# offical_board.net
KiCad netlist of a schematic drawn in EAGLE
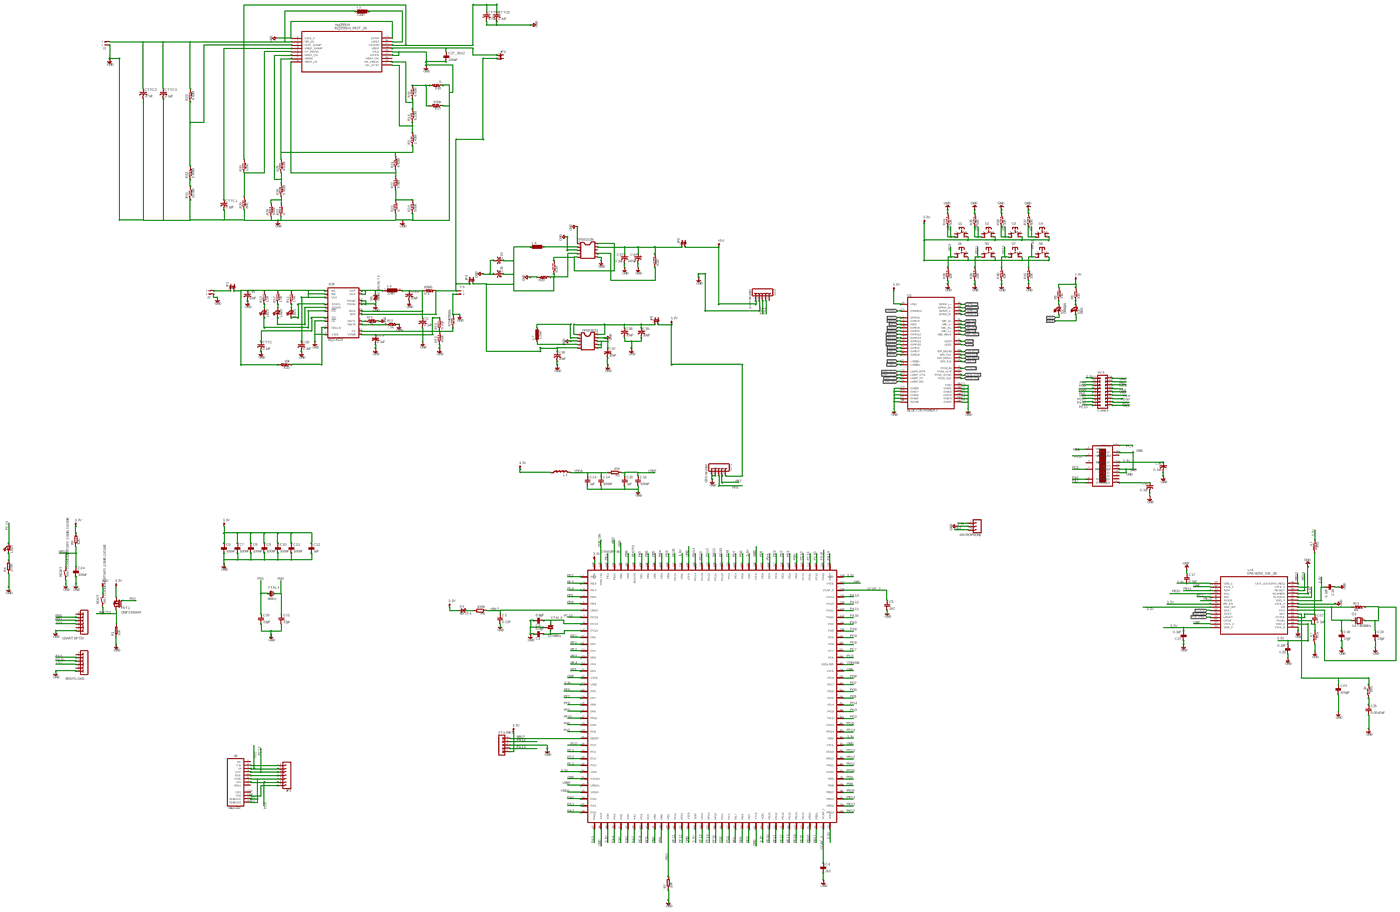
[diagram p0: schematic, sheet 1, overview]
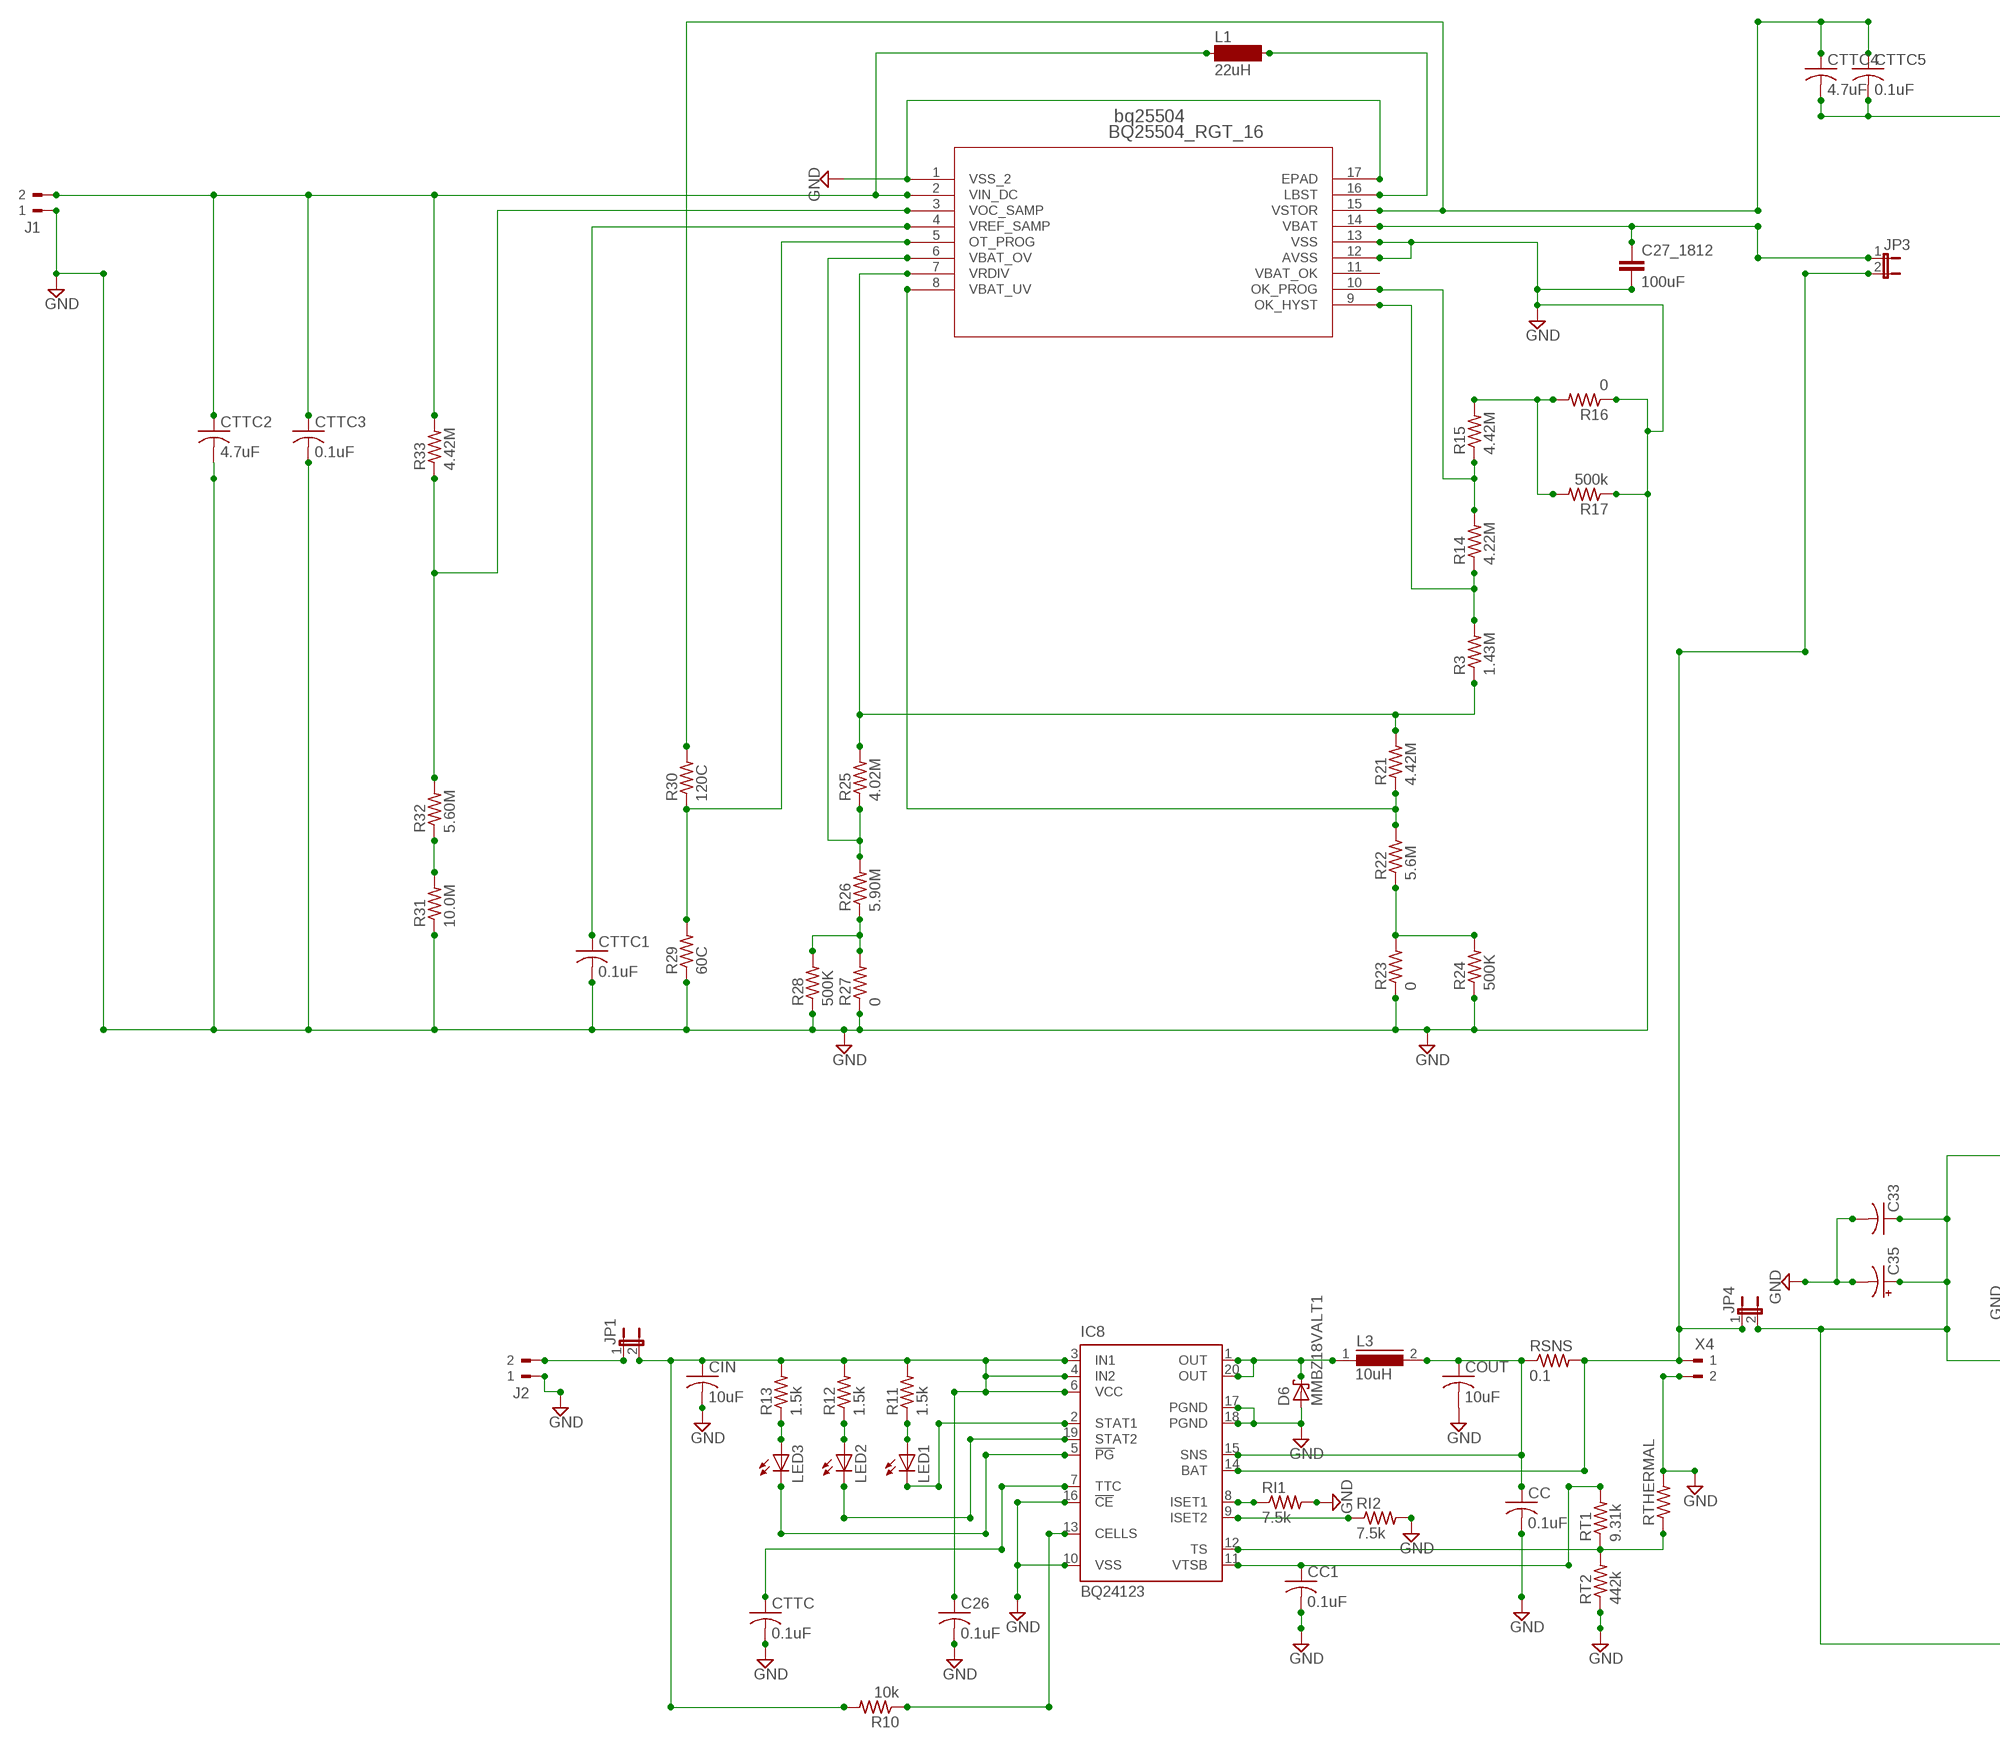
[diagram p1: schematic, sheet 1, part 1 of 5]
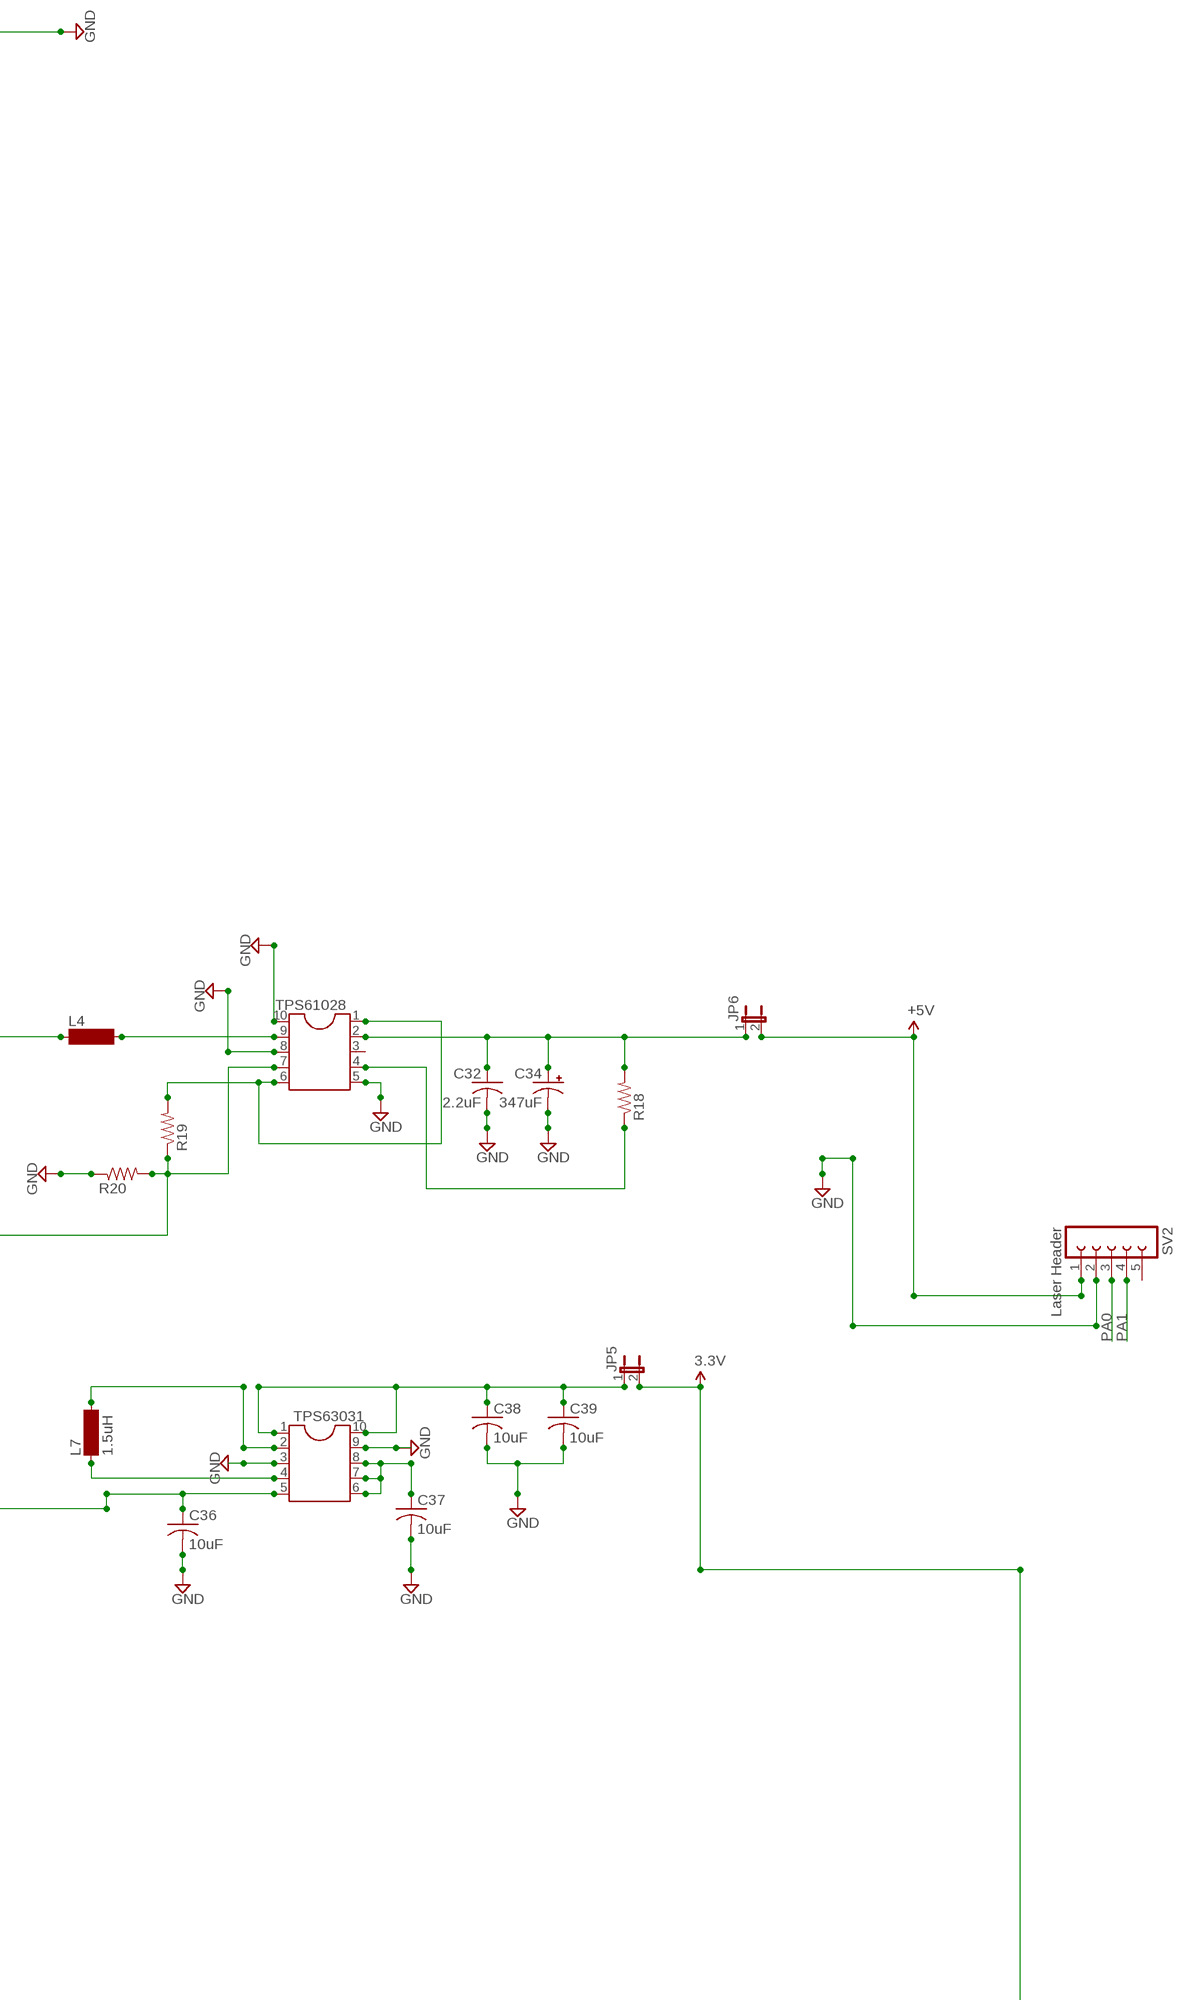
[diagram p2: schematic, sheet 1, part 2 of 5]
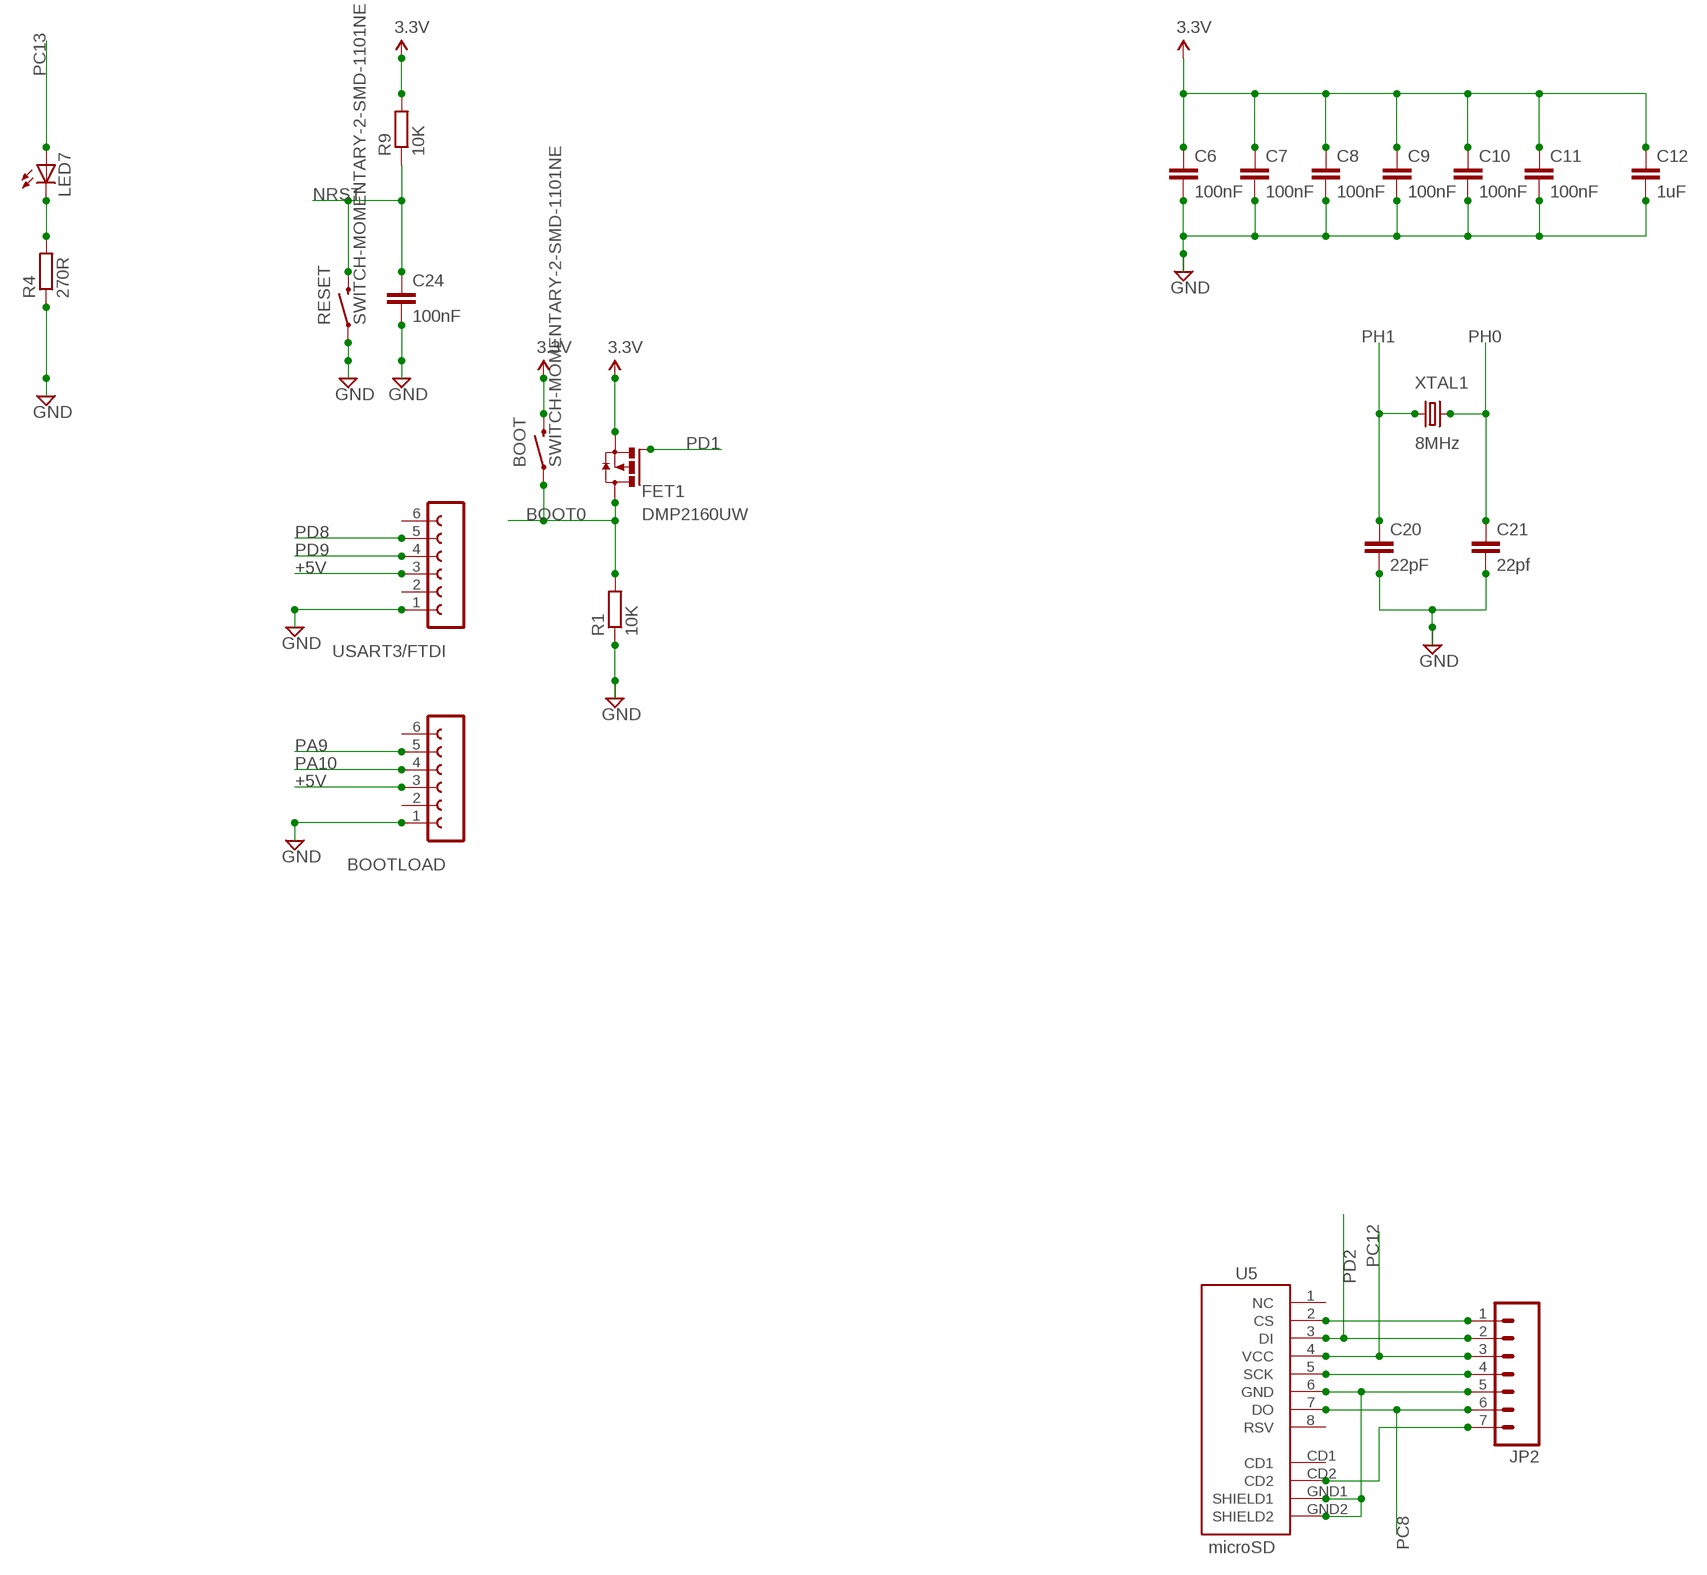
[diagram p3: schematic, sheet 1, part 3 of 5]
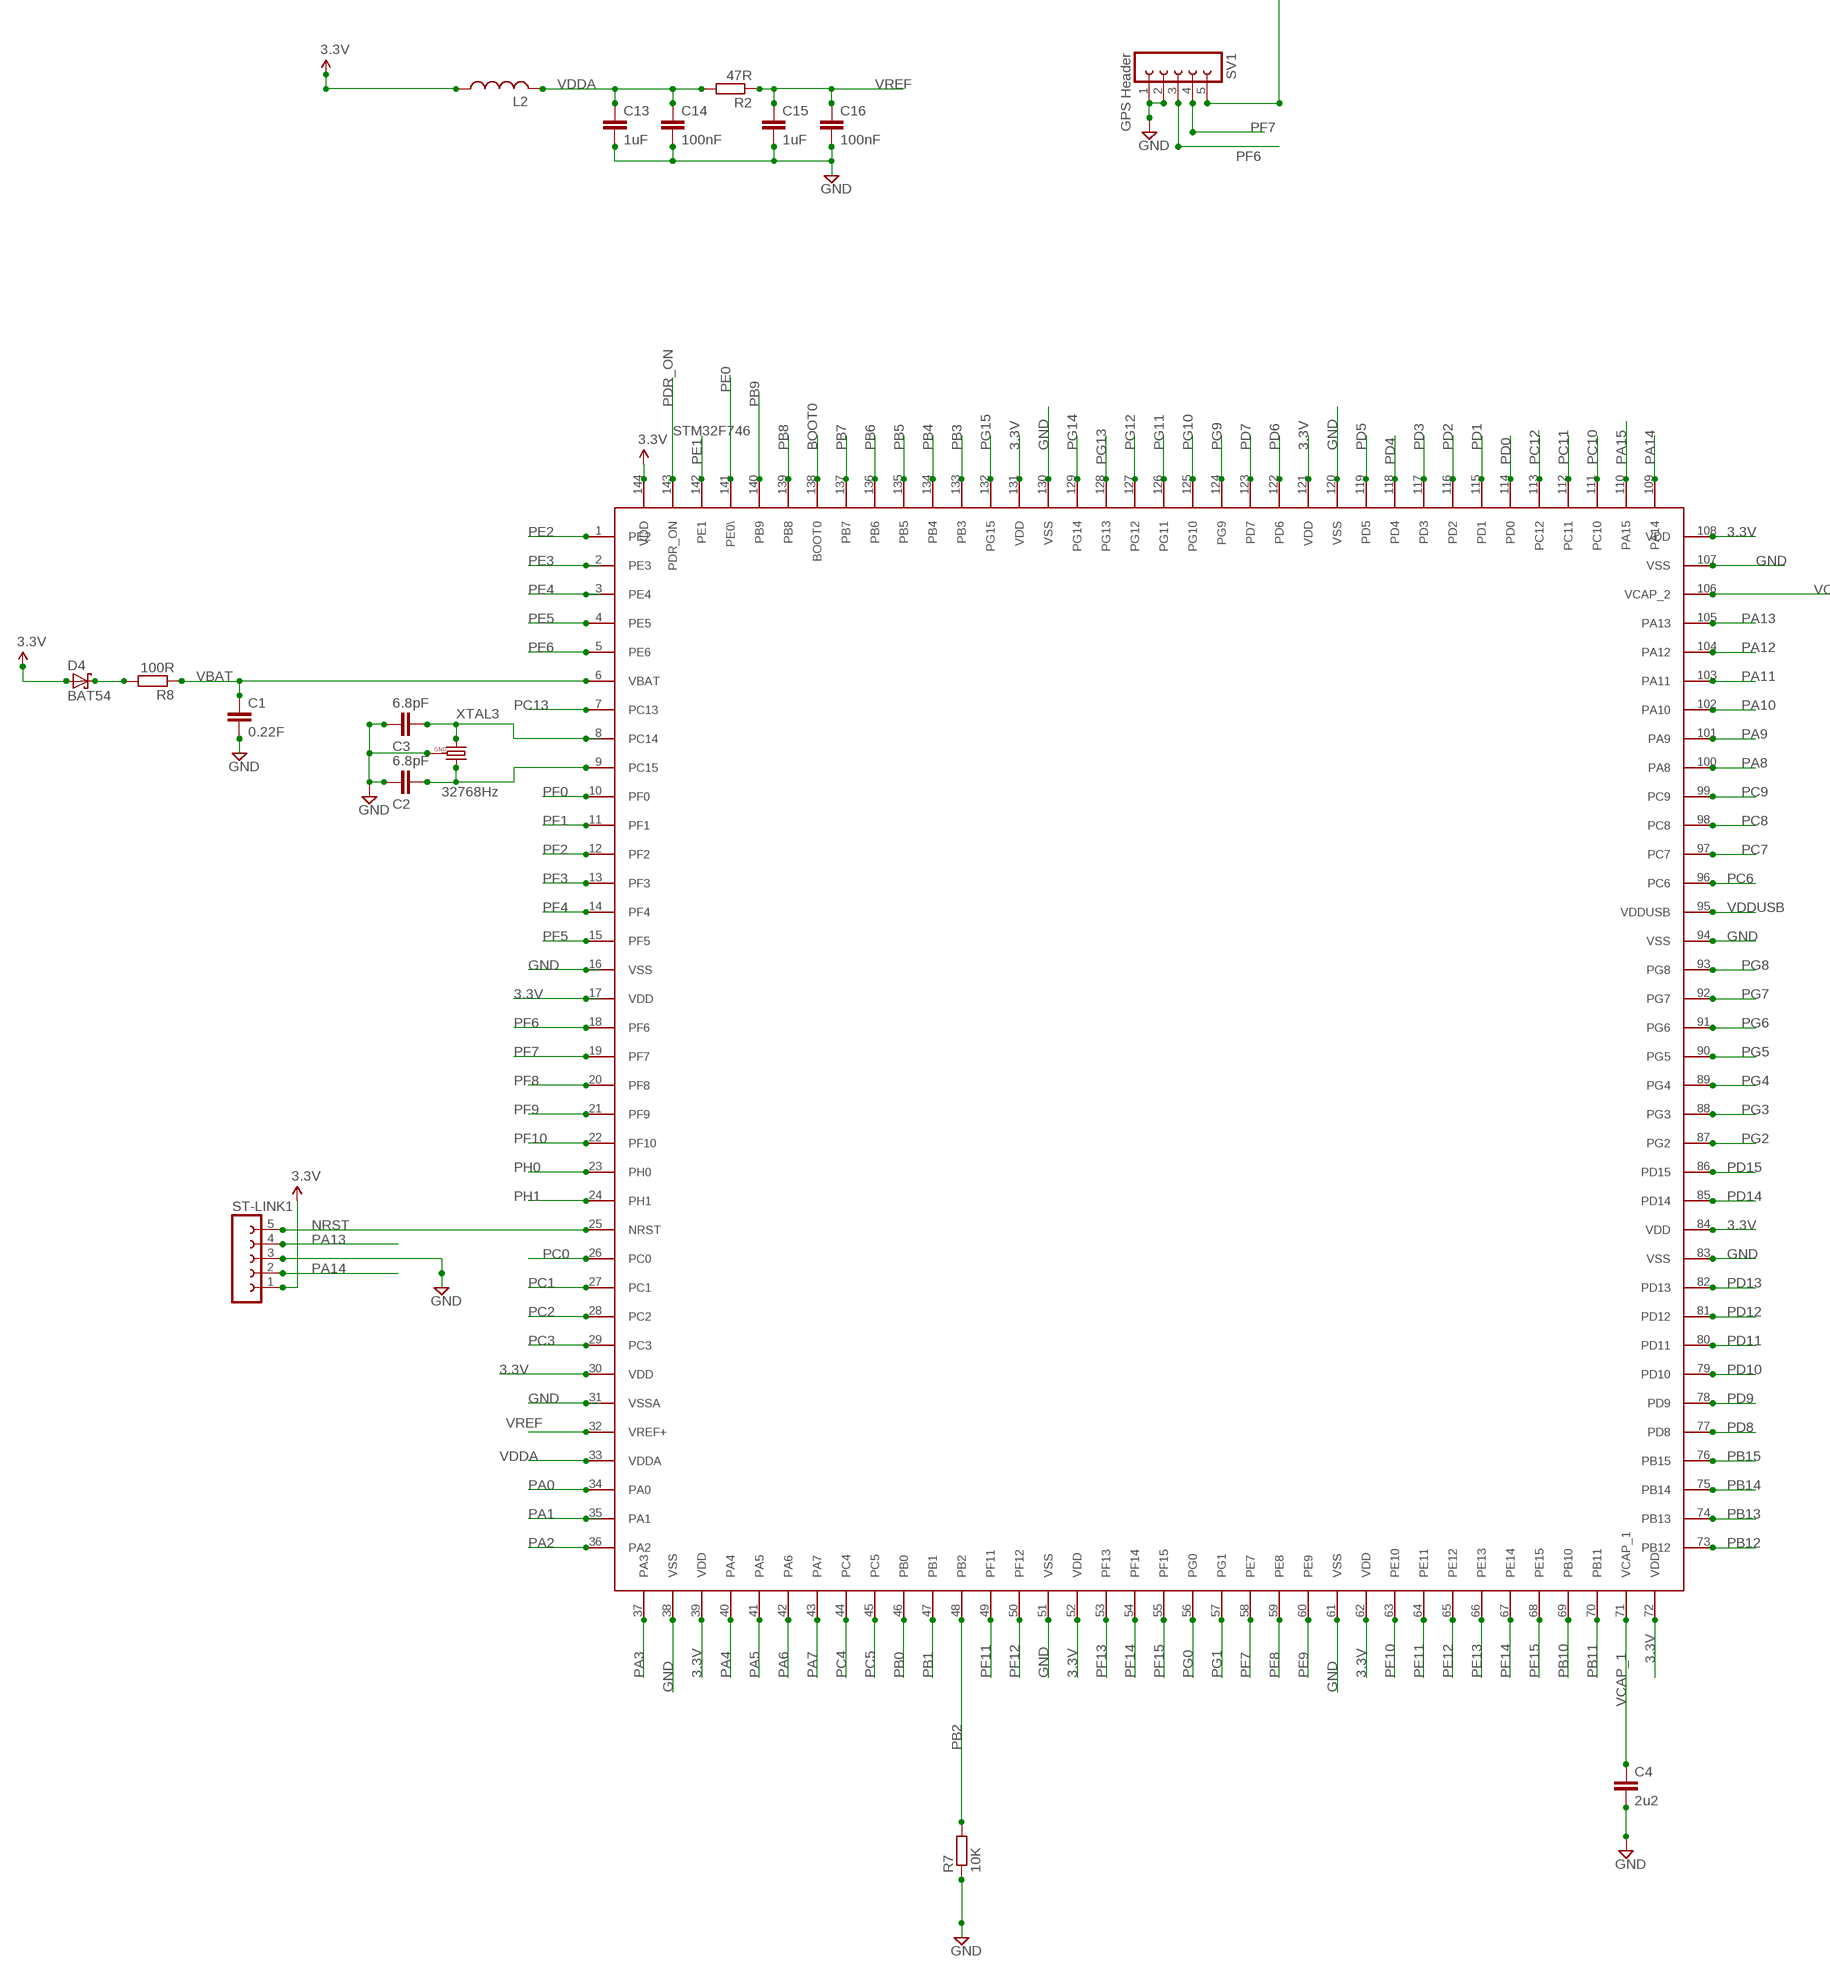
[diagram p4: schematic, sheet 1, part 4 of 5]
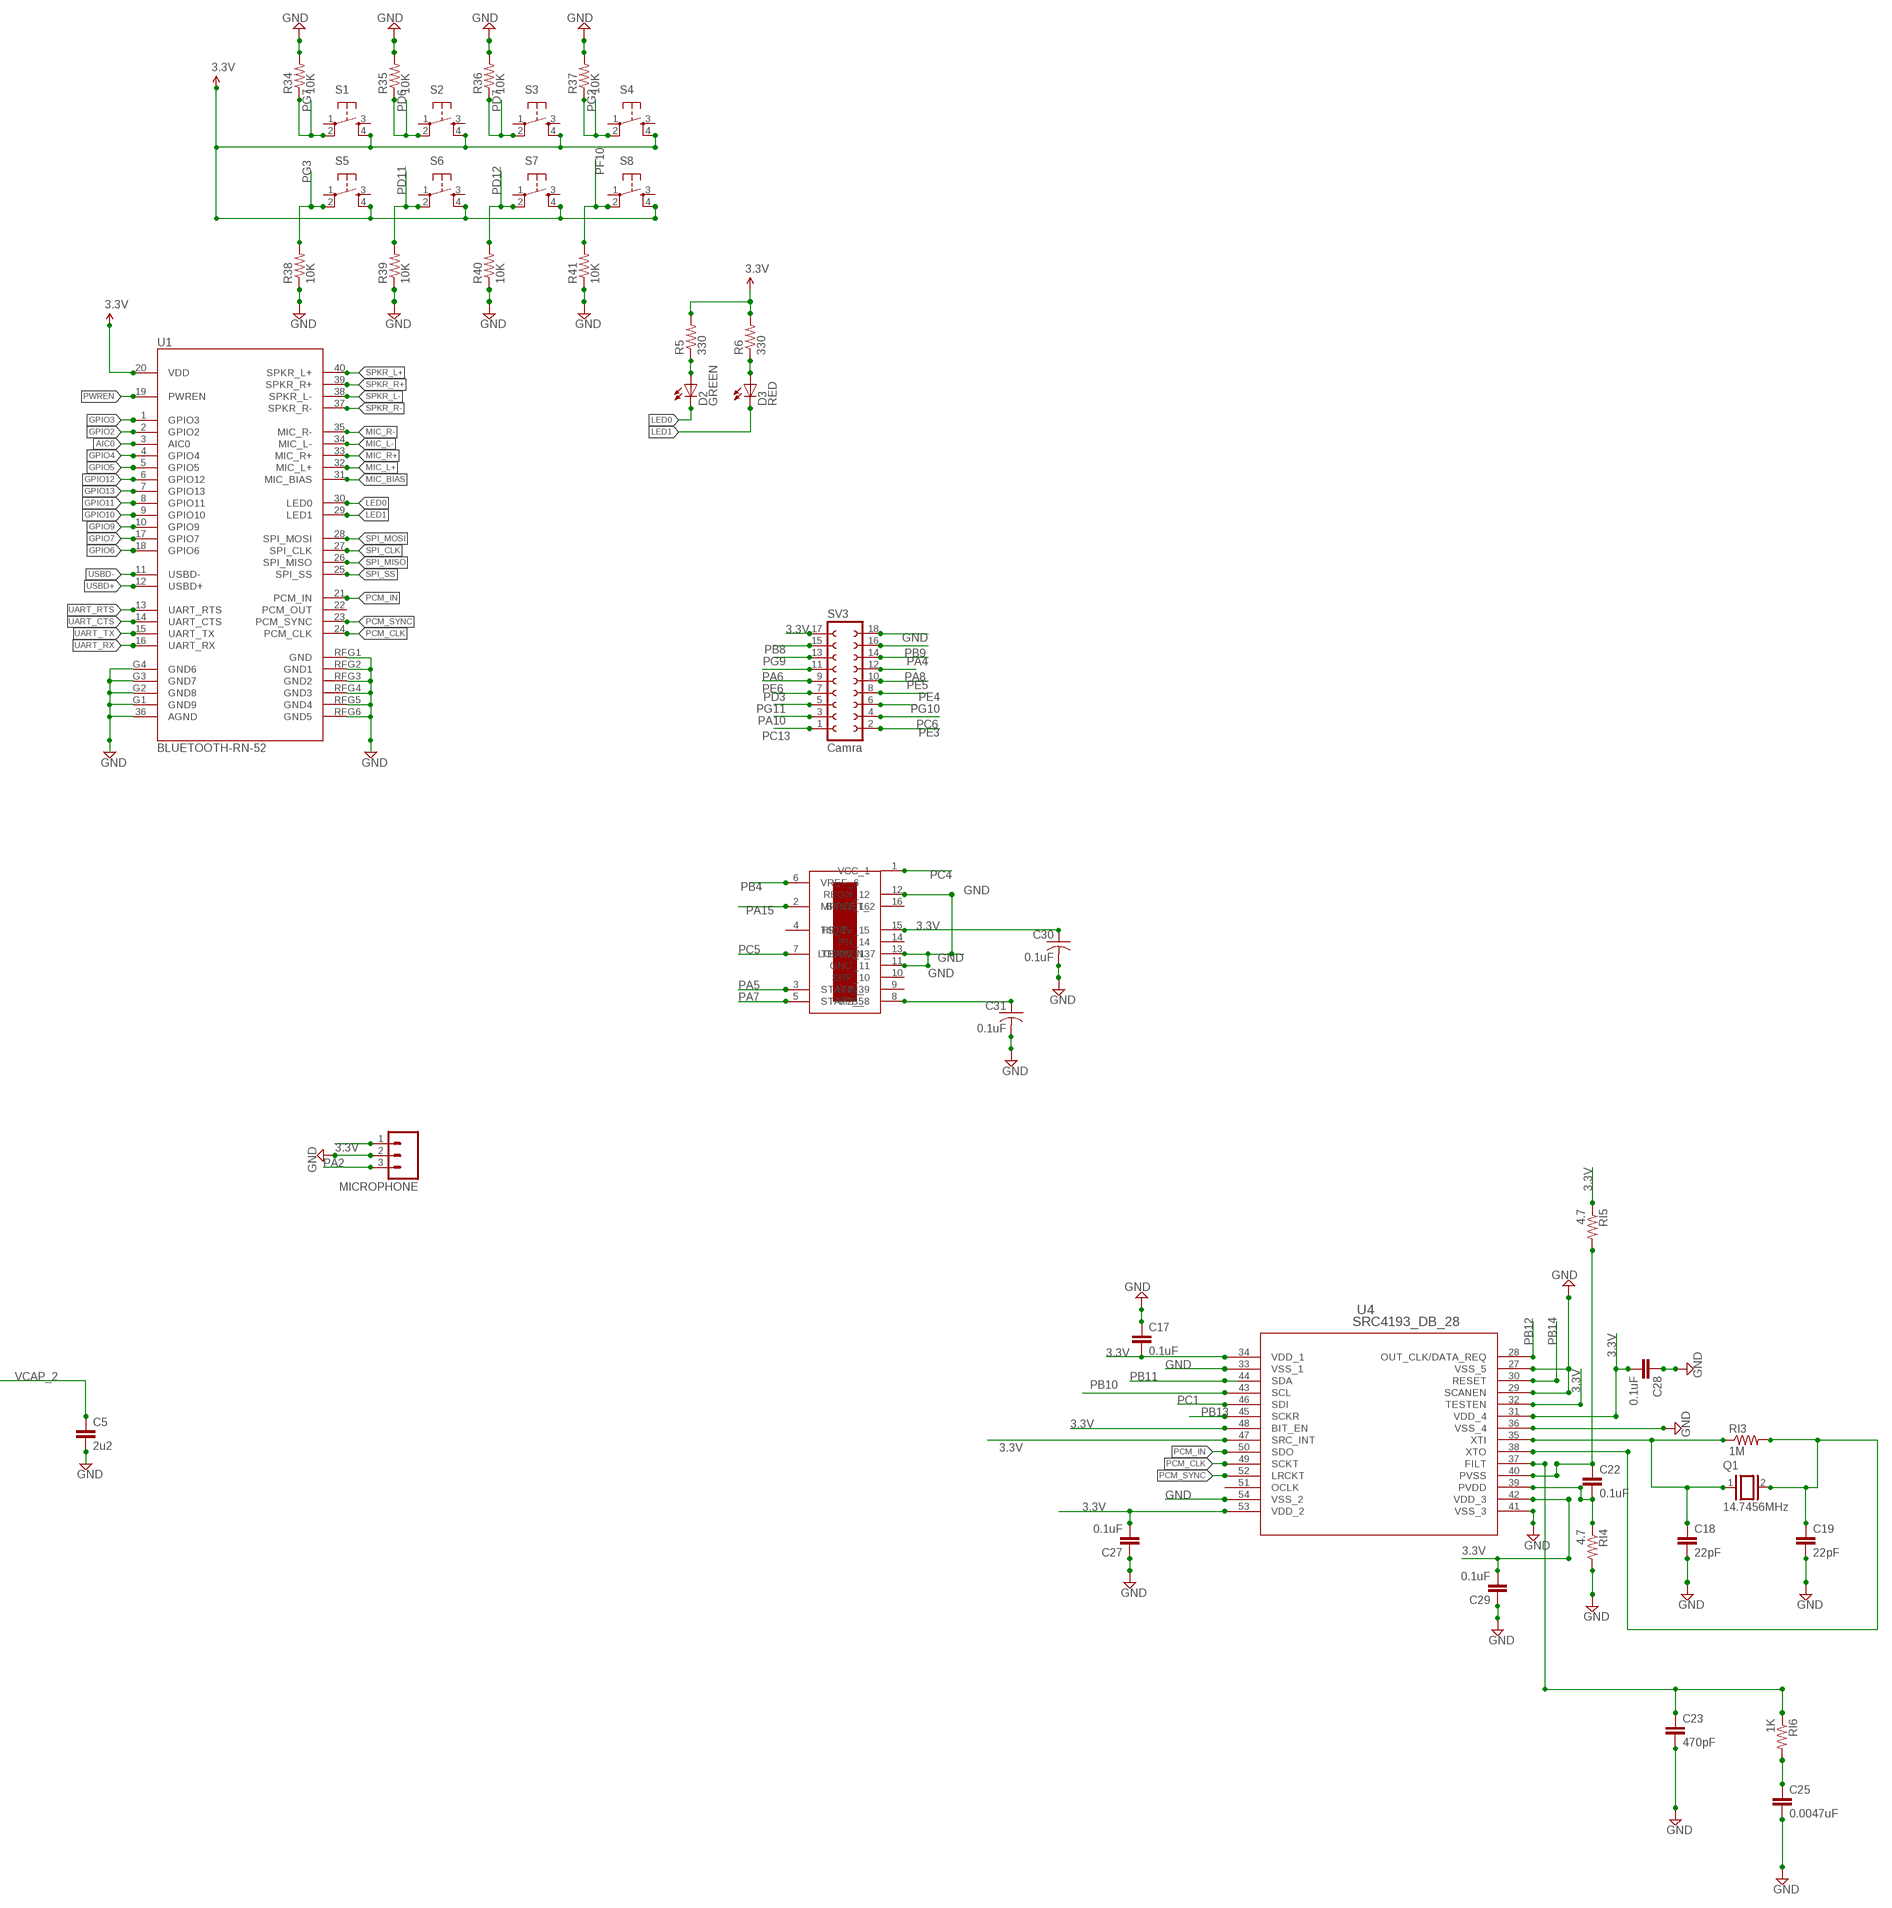
[diagram p5: schematic, sheet 1, part 5 of 5]

(export (version "E")
  (design (tool "Eeschema 10.0.6"))
  (components
    (comp (ref "BOOT")
      (value "SWITCH-MOMENTARY-2-SMD-1101NE")
      (footprint "eagle-import:TACTILE-SWITCH-1101NE")
      (libsource (lib "eagle-import") (part "SWITCH-MOMENTARY-2-SMD-1101NE"))
    )
    (comp (ref "BOOTLOAD")
      (value "FE06-1")
      (footprint "eagle-import:FE06")
      (libsource (lib "eagle-import") (part "FE06-1"))
    )
    (comp (ref "C1")
      (value "0.22F")
      (footprint "eagle-import:C5B5")
      (libsource (lib "eagle-import") (part "C5/5"))
    )
    (comp (ref "C2")
      (value "6.8pF")
      (footprint "eagle-import:C0603")
      (libsource (lib "eagle-import") (part "C-EUC0603"))
    )
    (comp (ref "C3")
      (value "6.8pF")
      (footprint "eagle-import:C0603")
      (libsource (lib "eagle-import") (part "C-EUC0603"))
    )
    (comp (ref "C4")
      (value "2u2")
      (footprint "eagle-import:C0603")
      (libsource (lib "eagle-import") (part "C-EUC0603"))
    )
    (comp (ref "C5")
      (value "2u2")
      (footprint "eagle-import:C0603")
      (libsource (lib "eagle-import") (part "C-EUC0603"))
    )
    (comp (ref "C6")
      (value "100nF")
      (footprint "eagle-import:C0603")
      (libsource (lib "eagle-import") (part "C-EUC0603"))
    )
    (comp (ref "C7")
      (value "100nF")
      (footprint "eagle-import:C0603")
      (libsource (lib "eagle-import") (part "C-EUC0603"))
    )
    (comp (ref "C8")
      (value "100nF")
      (footprint "eagle-import:C0603")
      (libsource (lib "eagle-import") (part "C-EUC0603"))
    )
    (comp (ref "C9")
      (value "100nF")
      (footprint "eagle-import:C0603")
      (libsource (lib "eagle-import") (part "C-EUC0603"))
    )
    (comp (ref "C10")
      (value "100nF")
      (footprint "eagle-import:C0603")
      (libsource (lib "eagle-import") (part "C-EUC0603"))
    )
    (comp (ref "C11")
      (value "100nF")
      (footprint "eagle-import:C0603")
      (libsource (lib "eagle-import") (part "C-EUC0603"))
    )
    (comp (ref "C12")
      (value "1uF")
      (footprint "eagle-import:C0603")
      (libsource (lib "eagle-import") (part "C-EUC0603"))
    )
    (comp (ref "C13")
      (value "1uF")
      (footprint "eagle-import:C0603")
      (libsource (lib "eagle-import") (part "C-EUC0603"))
    )
    (comp (ref "C14")
      (value "100nF")
      (footprint "eagle-import:C0603")
      (libsource (lib "eagle-import") (part "C-EUC0603"))
    )
    (comp (ref "C15")
      (value "1uF")
      (footprint "eagle-import:C0603")
      (libsource (lib "eagle-import") (part "C-EUC0603"))
    )
    (comp (ref "C16")
      (value "100nF")
      (footprint "eagle-import:C0603")
      (libsource (lib "eagle-import") (part "C-EUC0603"))
    )
    (comp (ref "C17")
      (value "0.1uF")
      (footprint "eagle-import:C0603")
      (libsource (lib "eagle-import") (part "C-EUC0603"))
    )
    (comp (ref "C18")
      (value "22pF")
      (footprint "eagle-import:C0603")
      (libsource (lib "eagle-import") (part "C-EUC0603"))
    )
    (comp (ref "C19")
      (value "22pF")
      (footprint "eagle-import:C0603")
      (libsource (lib "eagle-import") (part "C-EUC0603"))
    )
    (comp (ref "C20")
      (value "22pF")
      (footprint "eagle-import:C0603")
      (libsource (lib "eagle-import") (part "C-EUC0603"))
    )
    (comp (ref "C21")
      (value "22pf")
      (footprint "eagle-import:C0603")
      (libsource (lib "eagle-import") (part "C-EUC0603"))
    )
    (comp (ref "C22")
      (value "0.1uF")
      (footprint "eagle-import:C0603")
      (libsource (lib "eagle-import") (part "C-EUC0603"))
    )
    (comp (ref "C23")
      (value "470pF")
      (footprint "eagle-import:C0603")
      (libsource (lib "eagle-import") (part "C-EUC0603"))
    )
    (comp (ref "C24")
      (value "100nF")
      (footprint "eagle-import:C0603")
      (libsource (lib "eagle-import") (part "C-EUC0603"))
    )
    (comp (ref "C25")
      (value "0.0047uF")
      (footprint "eagle-import:C0603")
      (libsource (lib "eagle-import") (part "C-EUC0603"))
    )
    (comp (ref "C26")
      (value "0.1uF")
      (footprint "eagle-import:C0805")
      (libsource (lib "eagle-import") (part "C-USC0805"))
    )
    (comp (ref "C27")
      (value "0.1uF")
      (footprint "eagle-import:C0603")
      (libsource (lib "eagle-import") (part "C-EUC0603"))
    )
    (comp (ref "C27_1812")
      (value "100uF")
      (footprint "eagle-import:C1812")
      (libsource (lib "eagle-import") (part "resistor_C-EUC1812"))
    )
    (comp (ref "C28")
      (value "0.1uF")
      (footprint "eagle-import:C0603")
      (libsource (lib "eagle-import") (part "C-EUC0603"))
    )
    (comp (ref "C29")
      (value "0.1uF")
      (footprint "eagle-import:C0603")
      (libsource (lib "eagle-import") (part "C-EUC0603"))
    )
    (comp (ref "C30")
      (value "0.1uF")
      (footprint "eagle-import:C0603")
      (libsource (lib "eagle-import") (part "C-USC0603"))
    )
    (comp (ref "C31")
      (value "0.1uF")
      (footprint "eagle-import:C0603")
      (libsource (lib "eagle-import") (part "C-USC0603"))
    )
    (comp (ref "C32")
      (value "2.2uF")
      (footprint "eagle-import:C0603")
      (libsource (lib "eagle-import") (part "C-USC0603"))
    )
    (comp (ref "C33")
      (value "C-USC0603")
      (footprint "eagle-import:C0603")
      (libsource (lib "eagle-import") (part "C-USC0603"))
    )
    (comp (ref "C34")
      (value "347uF")
      (footprint "eagle-import:150CLZ-0810")
      (libsource (lib "eagle-import") (part "CPOL-US150CLZ-0810"))
    )
    (comp (ref "C35")
      (value "CPOL-US150CLZ-0810")
      (footprint "eagle-import:150CLZ-0810")
      (libsource (lib "eagle-import") (part "CPOL-US150CLZ-0810"))
    )
    (comp (ref "C36")
      (value "10uF")
      (footprint "eagle-import:C0603")
      (libsource (lib "eagle-import") (part "C-USC0603"))
    )
    (comp (ref "C37")
      (value "10uF")
      (footprint "eagle-import:C0603")
      (libsource (lib "eagle-import") (part "C-USC0603"))
    )
    (comp (ref "C38")
      (value "10uF")
      (footprint "eagle-import:C0603")
      (libsource (lib "eagle-import") (part "C-USC0603"))
    )
    (comp (ref "C39")
      (value "10uF")
      (footprint "eagle-import:C0603")
      (libsource (lib "eagle-import") (part "C-USC0603"))
    )
    (comp (ref "CC")
      (value "0.1uF")
      (footprint "eagle-import:C0805")
      (libsource (lib "eagle-import") (part "C-USC0805"))
    )
    (comp (ref "CC1")
      (value "0.1uF")
      (footprint "eagle-import:C0805")
      (libsource (lib "eagle-import") (part "C-USC0805"))
    )
    (comp (ref "CIN")
      (value "10uF")
      (footprint "eagle-import:C0805")
      (libsource (lib "eagle-import") (part "C-USC0805"))
    )
    (comp (ref "COUT")
      (value "10uF")
      (footprint "eagle-import:C0805")
      (libsource (lib "eagle-import") (part "C-USC0805"))
    )
    (comp (ref "CTTC")
      (value "0.1uF")
      (footprint "eagle-import:C0805")
      (libsource (lib "eagle-import") (part "C-USC0805"))
    )
    (comp (ref "CTTC1")
      (value "0.1uF")
      (footprint "eagle-import:C0805")
      (libsource (lib "eagle-import") (part "C-USC0805"))
    )
    (comp (ref "CTTC2")
      (value "4.7uF")
      (footprint "eagle-import:C0805")
      (libsource (lib "eagle-import") (part "C-USC0805"))
    )
    (comp (ref "CTTC3")
      (value "0.1uF")
      (footprint "eagle-import:C0805")
      (libsource (lib "eagle-import") (part "C-USC0805"))
    )
    (comp (ref "CTTC4")
      (value "4.7uF")
      (footprint "eagle-import:C0805")
      (libsource (lib "eagle-import") (part "C-USC0805"))
    )
    (comp (ref "CTTC5")
      (value "0.1uF")
      (footprint "eagle-import:C0805")
      (libsource (lib "eagle-import") (part "C-USC0805"))
    )
    (comp (ref "D2")
      (value "GREEN")
      (footprint "eagle-import:LED-0603")
      (libsource (lib "eagle-import") (part "LED-GREEN0603"))
    )
    (comp (ref "D3")
      (value "RED")
      (footprint "eagle-import:LED-0603")
      (libsource (lib "eagle-import") (part "LED-RED0603"))
    )
    (comp (ref "D4")
      (value "BAT54")
      (footprint "eagle-import:SOT23")
      (libsource (lib "eagle-import") (part "BAT54"))
    )
    (comp (ref "D6")
      (value "MMBZ18VALT1")
      (footprint "eagle-import:C4111-15")
      (libsource (lib "eagle-import") (part "1N5908"))
    )
    (comp (ref "FET1")
      (value "DMP2160UW")
      (footprint "eagle-import:SUPER-SOT3")
      (libsource (lib "eagle-import") (part "FDN360P"))
    )
    (comp (ref "IC8")
      (value "BQ24123")
      (footprint "eagle-import:QFN20_3,5X4,5")
      (fields (field (name "MPN") "BQ24123RHLT"))
      (libsource (lib "eagle-import") (part "BQ24123"))
    )
    (comp (ref "J1")
      (value "90-2")
      (footprint "eagle-import:90-2")
      (libsource (lib "eagle-import") (part "90-2"))
    )
    (comp (ref "J2")
      (value "90-2")
      (footprint "eagle-import:90-2")
      (libsource (lib "eagle-import") (part "90-2"))
    )
    (comp (ref "JP1")
      (value "JP1E")
      (footprint "eagle-import:JP1")
      (libsource (lib "eagle-import") (part "JP1E"))
    )
    (comp (ref "JP2")
      (value "M07")
      (footprint "eagle-import:1X07")
      (libsource (lib "eagle-import") (part "M07"))
    )
    (comp (ref "JP3")
      (value "JP1E")
      (footprint "eagle-import:JP1")
      (libsource (lib "eagle-import") (part "JP1E"))
    )
    (comp (ref "JP4")
      (value "JP1E")
      (footprint "eagle-import:JP1")
      (libsource (lib "eagle-import") (part "JP1E"))
    )
    (comp (ref "JP5")
      (value "JP1E")
      (footprint "eagle-import:JP1")
      (libsource (lib "eagle-import") (part "JP1E"))
    )
    (comp (ref "JP6")
      (value "JP1E")
      (footprint "eagle-import:JP1")
      (libsource (lib "eagle-import") (part "JP1E"))
    )
    (comp (ref "L1")
      (value "22uH")
      (footprint "eagle-import:SM-1206")
      (libsource (lib "eagle-import") (part "SM-1206"))
    )
    (comp (ref "L2")
      (value "RCL_L-USL0603")
      (footprint "eagle-import:RCL_L0603")
      (libsource (lib "eagle-import") (part "RCL_L-USL0603"))
    )
    (comp (ref "L3")
      (value "10uH")
      (footprint "eagle-import:DR73")
      (libsource (lib "eagle-import") (part "DR73"))
    )
    (comp (ref "L4")
      (value "SM-1206")
      (footprint "eagle-import:SM-1206")
      (libsource (lib "eagle-import") (part "SM-1206"))
    )
    (comp (ref "L7")
      (value "1.5uH")
      (footprint "eagle-import:SM-1206")
      (libsource (lib "eagle-import") (part "SM-1206"))
    )
    (comp (ref "LED1")
      (value "SFH482")
      (footprint "eagle-import:SFH482")
      (libsource (lib "eagle-import") (part "SFH482"))
    )
    (comp (ref "LED2")
      (value "SFH482")
      (footprint "eagle-import:SFH482")
      (libsource (lib "eagle-import") (part "SFH482"))
    )
    (comp (ref "LED3")
      (value "SFH482")
      (footprint "eagle-import:SFH482")
      (libsource (lib "eagle-import") (part "SFH482"))
    )
    (comp (ref "LED7")
      (value "LEDCHIP-LED0603")
      (footprint "eagle-import:CHIP-LED0603")
      (libsource (lib "eagle-import") (part "LEDCHIP-LED0603"))
    )
    (comp (ref "MICROPHONE")
      (value "M03PTH")
      (footprint "eagle-import:1X03")
      (libsource (lib "eagle-import") (part "M03PTH"))
    )
    (comp (ref "Q1")
      (value "14.7456MHz")
      (footprint "eagle-import:QS")
      (libsource (lib "eagle-import") (part "XTAL/S"))
    )
    (comp (ref "R1")
      (value "10K")
      (footprint "eagle-import:R0603")
      (libsource (lib "eagle-import") (part "R-EU_R0603"))
    )
    (comp (ref "R2")
      (value "47R")
      (footprint "eagle-import:R0603")
      (libsource (lib "eagle-import") (part "R-EU_R0603"))
    )
    (comp (ref "R3")
      (value "1.43M")
      (footprint "eagle-import:R0805")
      (libsource (lib "eagle-import") (part "R-US_R0805"))
    )
    (comp (ref "R4")
      (value "270R")
      (footprint "eagle-import:R0603")
      (libsource (lib "eagle-import") (part "resistor_R-EU_R0603"))
    )
    (comp (ref "R5")
      (value "330")
      (footprint "eagle-import:0603-RES")
      (libsource (lib "eagle-import") (part "RESISTOR0603-RES"))
    )
    (comp (ref "R6")
      (value "330")
      (footprint "eagle-import:0603-RES")
      (libsource (lib "eagle-import") (part "RESISTOR0603-RES"))
    )
    (comp (ref "R7")
      (value "10K")
      (footprint "eagle-import:R0603")
      (libsource (lib "eagle-import") (part "R-EU_R0603"))
    )
    (comp (ref "R8")
      (value "100R")
      (footprint "eagle-import:R0603")
      (libsource (lib "eagle-import") (part "resistor_R-EU_R0603"))
    )
    (comp (ref "R9")
      (value "10K")
      (footprint "eagle-import:R0603")
      (libsource (lib "eagle-import") (part "R-EU_R0603"))
    )
    (comp (ref "R10")
      (value "10k")
      (footprint "eagle-import:R0805")
      (libsource (lib "eagle-import") (part "R-US_R0805"))
    )
    (comp (ref "R11")
      (value "1.5k")
      (footprint "eagle-import:R0805")
      (libsource (lib "eagle-import") (part "R-US_R0805"))
    )
    (comp (ref "R12")
      (value "1.5k")
      (footprint "eagle-import:R0805")
      (libsource (lib "eagle-import") (part "R-US_R0805"))
    )
    (comp (ref "R13")
      (value "1.5k")
      (footprint "eagle-import:R0805")
      (libsource (lib "eagle-import") (part "R-US_R0805"))
    )
    (comp (ref "R14")
      (value "4.22M")
      (footprint "eagle-import:R0805")
      (libsource (lib "eagle-import") (part "R-US_R0805"))
    )
    (comp (ref "R15")
      (value "4.42M")
      (footprint "eagle-import:R0805")
      (libsource (lib "eagle-import") (part "R-US_R0805"))
    )
    (comp (ref "R16")
      (value "0")
      (footprint "eagle-import:R0805")
      (libsource (lib "eagle-import") (part "R-US_R0805"))
    )
    (comp (ref "R17")
      (value "500k")
      (footprint "eagle-import:R0805")
      (libsource (lib "eagle-import") (part "R-US_R0805"))
    )
    (comp (ref "R18")
      (value "R-US_R0603")
      (footprint "eagle-import:R0603")
      (libsource (lib "eagle-import") (part "R-US_R0603"))
    )
    (comp (ref "R19")
      (value "R-US_R0603")
      (footprint "eagle-import:R0603")
      (libsource (lib "eagle-import") (part "R-US_R0603"))
    )
    (comp (ref "R20")
      (value "R-US_R0603")
      (footprint "eagle-import:R0603")
      (libsource (lib "eagle-import") (part "R-US_R0603"))
    )
    (comp (ref "R21")
      (value "4.42M")
      (footprint "eagle-import:R0805")
      (libsource (lib "eagle-import") (part "R-US_R0805"))
    )
    (comp (ref "R22")
      (value "5.6M")
      (footprint "eagle-import:R0805")
      (libsource (lib "eagle-import") (part "R-US_R0805"))
    )
    (comp (ref "R23")
      (value "0")
      (footprint "eagle-import:R0805")
      (libsource (lib "eagle-import") (part "R-US_R0805"))
    )
    (comp (ref "R24")
      (value "500K")
      (footprint "eagle-import:R0805")
      (libsource (lib "eagle-import") (part "R-US_R0805"))
    )
    (comp (ref "R25")
      (value "4.02M")
      (footprint "eagle-import:R0805")
      (libsource (lib "eagle-import") (part "R-US_R0805"))
    )
    (comp (ref "R26")
      (value "5.90M")
      (footprint "eagle-import:R0805")
      (libsource (lib "eagle-import") (part "R-US_R0805"))
    )
    (comp (ref "R27")
      (value "0")
      (footprint "eagle-import:R0805")
      (libsource (lib "eagle-import") (part "R-US_R0805"))
    )
    (comp (ref "R28")
      (value "500K")
      (footprint "eagle-import:R0805")
      (libsource (lib "eagle-import") (part "R-US_R0805"))
    )
    (comp (ref "R29")
      (value "60C")
      (footprint "eagle-import:R0805")
      (libsource (lib "eagle-import") (part "R-US_R0805"))
    )
    (comp (ref "R30")
      (value "120C")
      (footprint "eagle-import:R0805")
      (libsource (lib "eagle-import") (part "R-US_R0805"))
    )
    (comp (ref "R31")
      (value "10.0M")
      (footprint "eagle-import:R0805")
      (libsource (lib "eagle-import") (part "R-US_R0805"))
    )
    (comp (ref "R32")
      (value "5.60M")
      (footprint "eagle-import:R0805")
      (libsource (lib "eagle-import") (part "R-US_R0805"))
    )
    (comp (ref "R33")
      (value "4.42M")
      (footprint "eagle-import:R0805")
      (libsource (lib "eagle-import") (part "R-US_R0805"))
    )
    (comp (ref "R34")
      (value "10K")
      (footprint "eagle-import:0603-RES")
      (libsource (lib "eagle-import") (part "RESISTOR0603-RES"))
    )
    (comp (ref "R35")
      (value "10K")
      (footprint "eagle-import:0603-RES")
      (libsource (lib "eagle-import") (part "RESISTOR0603-RES"))
    )
    (comp (ref "R36")
      (value "10K")
      (footprint "eagle-import:0603-RES")
      (libsource (lib "eagle-import") (part "RESISTOR0603-RES"))
    )
    (comp (ref "R37")
      (value "10K")
      (footprint "eagle-import:0603-RES")
      (libsource (lib "eagle-import") (part "RESISTOR0603-RES"))
    )
    (comp (ref "R38")
      (value "10K")
      (footprint "eagle-import:0603-RES")
      (libsource (lib "eagle-import") (part "RESISTOR0603-RES"))
    )
    (comp (ref "R39")
      (value "10K")
      (footprint "eagle-import:0603-RES")
      (libsource (lib "eagle-import") (part "RESISTOR0603-RES"))
    )
    (comp (ref "R40")
      (value "10K")
      (footprint "eagle-import:0603-RES")
      (libsource (lib "eagle-import") (part "RESISTOR0603-RES"))
    )
    (comp (ref "R41")
      (value "10K")
      (footprint "eagle-import:0603-RES")
      (libsource (lib "eagle-import") (part "RESISTOR0603-RES"))
    )
    (comp (ref "RESET")
      (value "SWITCH-MOMENTARY-2-SMD-1101NE")
      (footprint "eagle-import:TACTILE-SWITCH-1101NE")
      (libsource (lib "eagle-import") (part "SWITCH-MOMENTARY-2-SMD-1101NE"))
    )
    (comp (ref "RI1")
      (value "7.5k")
      (footprint "eagle-import:R0805")
      (libsource (lib "eagle-import") (part "R-US_R0805"))
    )
    (comp (ref "RI2")
      (value "7.5k")
      (footprint "eagle-import:R0805")
      (libsource (lib "eagle-import") (part "R-US_R0805"))
    )
    (comp (ref "RI3")
      (value "1M")
      (footprint "eagle-import:R0805")
      (libsource (lib "eagle-import") (part "R-US_R0805"))
    )
    (comp (ref "RI4")
      (value "4.7")
      (footprint "eagle-import:R0805")
      (libsource (lib "eagle-import") (part "R-US_R0805"))
    )
    (comp (ref "RI5")
      (value "4.7")
      (footprint "eagle-import:R0805")
      (libsource (lib "eagle-import") (part "R-US_R0805"))
    )
    (comp (ref "RI6")
      (value "1K")
      (footprint "eagle-import:R0805")
      (libsource (lib "eagle-import") (part "R-US_R0805"))
    )
    (comp (ref "RSNS")
      (value "0.1")
      (footprint "eagle-import:R1206")
      (libsource (lib "eagle-import") (part "R-US_R1206"))
    )
    (comp (ref "RT1")
      (value "9.31k")
      (footprint "eagle-import:R0805")
      (libsource (lib "eagle-import") (part "R-US_R0805"))
    )
    (comp (ref "RT2")
      (value "442k")
      (footprint "eagle-import:R0805")
      (libsource (lib "eagle-import") (part "R-US_R0805"))
    )
    (comp (ref "RTHERMAL")
      (value "R-US_R0805")
      (footprint "eagle-import:R0805")
      (libsource (lib "eagle-import") (part "R-US_R0805"))
    )
    (comp (ref "S1")
      (value "TAC_SWITCHSMD")
      (footprint "eagle-import:TACTILE_SWITCH_SMD")
      (libsource (lib "eagle-import") (part "TAC_SWITCHSMD"))
    )
    (comp (ref "S2")
      (value "TAC_SWITCHSMD")
      (footprint "eagle-import:TACTILE_SWITCH_SMD")
      (libsource (lib "eagle-import") (part "TAC_SWITCHSMD"))
    )
    (comp (ref "S3")
      (value "TAC_SWITCHSMD")
      (footprint "eagle-import:TACTILE_SWITCH_SMD")
      (libsource (lib "eagle-import") (part "TAC_SWITCHSMD"))
    )
    (comp (ref "S4")
      (value "TAC_SWITCHSMD")
      (footprint "eagle-import:TACTILE_SWITCH_SMD")
      (libsource (lib "eagle-import") (part "TAC_SWITCHSMD"))
    )
    (comp (ref "S5")
      (value "TAC_SWITCHSMD")
      (footprint "eagle-import:TACTILE_SWITCH_SMD")
      (libsource (lib "eagle-import") (part "TAC_SWITCHSMD"))
    )
    (comp (ref "S6")
      (value "TAC_SWITCHSMD")
      (footprint "eagle-import:TACTILE_SWITCH_SMD")
      (libsource (lib "eagle-import") (part "TAC_SWITCHSMD"))
    )
    (comp (ref "S7")
      (value "TAC_SWITCHSMD")
      (footprint "eagle-import:TACTILE_SWITCH_SMD")
      (libsource (lib "eagle-import") (part "TAC_SWITCHSMD"))
    )
    (comp (ref "S8")
      (value "TAC_SWITCHSMD")
      (footprint "eagle-import:TACTILE_SWITCH_SMD")
      (libsource (lib "eagle-import") (part "TAC_SWITCHSMD"))
    )
    (comp (ref "ST-LINK1")
      (value "FE05-1")
      (footprint "eagle-import:FE05-1")
      (libsource (lib "eagle-import") (part "FE05-1"))
    )
    (comp (ref "SV1")
      (value "GPS Header")
      (footprint "eagle-import:FE05-1")
      (libsource (lib "eagle-import") (part "FE05-1"))
    )
    (comp (ref "SV2")
      (value "Laser Header")
      (footprint "eagle-import:FE05-1")
      (libsource (lib "eagle-import") (part "FE05-1"))
    )
    (comp (ref "SV3")
      (value "Camra")
      (footprint "eagle-import:FE09-2")
      (libsource (lib "eagle-import") (part "FE09-2"))
    )
    (comp (ref "TPS61028")
      (value "DIL10")
      (footprint "eagle-import:DIL10")
      (libsource (lib "eagle-import") (part "DIL10"))
    )
    (comp (ref "TPS63031")
      (value "DIL10")
      (footprint "eagle-import:DIL10")
      (libsource (lib "eagle-import") (part "DIL10"))
    )
    (comp (ref "U$1")
      (value "STM32F746")
      (footprint "eagle-import:QFN144")
      (libsource (lib "eagle-import") (part "STM32F746"))
    )
    (comp (ref "U$2")
      (value "QFN16")
      (footprint "eagle-import:QFN16")
      (libsource (lib "eagle-import") (part "QFN16"))
    )
    (comp (ref "U1")
      (value "BLUETOOTH-RN-52")
      (footprint "eagle-import:RN-52")
      (libsource (lib "eagle-import") (part "BLUETOOTH-RN-52"))
    )
    (comp (ref "U3")
      (value "BQ25504_RGT_16")
      (footprint "eagle-import:RGT16_1P7X1P7")
      (fields
        (field (name "GENERIC_PART_NUMBER") "BQ25504")
        (field (name "MANUFACTURER") "Texas Instruments")
      )
      (libsource (lib "eagle-import") (part "BQ25504_RGT_16"))
    )
    (comp (ref "U4")
      (value "SRC4193_DB_28")
      (footprint "eagle-import:DB28")
      (fields
        (field (name "GENERIC_PART_NUMBER") "SRC4193")
        (field (name "MANUFACTURER") "Texas Instruments")
        (field (name "MANUFACTURER_PART_NUMBER") "src4193_db_28")
      )
      (libsource (lib "eagle-import") (part "SRC4193_DB_28"))
    )
    (comp (ref "U5")
      (value "microSD")
      (footprint "eagle-import:MICRO-SD-SOCKET-PP")
      (libsource (lib "eagle-import") (part "USD-SOCKETSMD"))
    )
    (comp (ref "USART3/FTDI")
      (value "FE06-1")
      (footprint "eagle-import:FE06")
      (libsource (lib "eagle-import") (part "FE06-1"))
    )
    (comp (ref "X4")
      (value "90-2")
      (footprint "eagle-import:90-2")
      (libsource (lib "eagle-import") (part "90-2"))
    )
    (comp (ref "XTAL1")
      (value "8MHz")
      (footprint "eagle-import:HC49U-V")
      (libsource (lib "eagle-import") (part "CRYSTALHC49U-V"))
    )
    (comp (ref "XTAL3")
      (value "32768Hz")
      (footprint "eagle-import:CRYSTAL_TC26H_3_REPAIR_SMD_SMALL_PITCH")
      (libsource (lib "eagle-import") (part "CRYSTAL_Q_GNDS"))
    )
  )
  (nets
    (net (code "1") (name "+5V") (class "Default")
      (node (ref "BOOTLOAD") (pin "3") (pinfunction "3_3") (pintype "passive"))
      (node (ref "JP6") (pin "2") (pinfunction "2_2") (pintype "passive"))
      (node (ref "SV2") (pin "1") (pinfunction "1_1") (pintype "passive"))
      (node (ref "USART3/FTDI") (pin "3") (pinfunction "3_3") (pintype "passive"))
    )
    (net (code "2") (name "/BOOT0") (class "Default")
      (node (ref "BOOT") (pin "P$1") (pinfunction "1_P$1") (pintype "passive"))
      (node (ref "FET1") (pin "3") (pinfunction "D_3") (pintype "passive"))
      (node (ref "R1") (pin "2") (pinfunction "2_2") (pintype "passive"))
      (node (ref "U$1") (pin "138") (pinfunction "BOOT0_138") (pintype "bidirectional"))
    )
    (net (code "3") (name "/NRST") (class "Default")
      (node (ref "C24") (pin "1") (pinfunction "1_1") (pintype "passive"))
      (node (ref "R9") (pin "1") (pinfunction "1_1") (pintype "passive"))
      (node (ref "RESET") (pin "P$2") (pinfunction "2_P$2") (pintype "passive"))
      (node (ref "ST-LINK1") (pin "5") (pinfunction "5_5") (pintype "passive"))
      (node (ref "U$1") (pin "25") (pinfunction "NRST_25") (pintype "bidirectional"))
    )
    (net (code "4") (name "/PA0") (class "Default")
      (node (ref "SV2") (pin "3") (pinfunction "3_3") (pintype "passive"))
      (node (ref "U$1") (pin "34") (pinfunction "PA0_34") (pintype "bidirectional"))
    )
    (net (code "5") (name "/PA1") (class "Default")
      (node (ref "SV2") (pin "4") (pinfunction "4_4") (pintype "passive"))
      (node (ref "U$1") (pin "35") (pinfunction "PA1_35") (pintype "bidirectional"))
    )
    (net (code "6") (name "/PA2") (class "Default")
      (node (ref "MICROPHONE") (pin "3") (pinfunction "3_3") (pintype "passive"))
      (node (ref "U$1") (pin "36") (pinfunction "PA2_36") (pintype "bidirectional"))
    )
    (net (code "7") (name "/PA3") (class "Default")
      (node (ref "U$1") (pin "37") (pinfunction "PA3_37") (pintype "bidirectional"))
    )
    (net (code "8") (name "/PA4") (class "Default")
      (node (ref "SV3") (pin "14") (pinfunction "14_14") (pintype "passive"))
      (node (ref "U$1") (pin "40") (pinfunction "PA4_40") (pintype "bidirectional"))
    )
    (net (code "9") (name "/PA5") (class "Default")
      (node (ref "U$1") (pin "41") (pinfunction "PA5_41") (pintype "bidirectional"))
      (node (ref "U$2") (pin "3") (pinfunction "STAT1_3_3") (pintype "bidirectional"))
    )
    (net (code "10") (name "/PA6") (class "Default")
      (node (ref "SV3") (pin "11") (pinfunction "11_11") (pintype "passive"))
      (node (ref "U$1") (pin "42") (pinfunction "PA6_42") (pintype "bidirectional"))
    )
    (net (code "11") (name "/PA7") (class "Default")
      (node (ref "U$1") (pin "43") (pinfunction "PA7_43") (pintype "bidirectional"))
      (node (ref "U$2") (pin "5") (pinfunction "STAT2_5_5") (pintype "bidirectional"))
    )
    (net (code "12") (name "/PA8") (class "Default")
      (node (ref "SV3") (pin "12") (pinfunction "12_12") (pintype "passive"))
      (node (ref "U$1") (pin "100") (pinfunction "PA8_100") (pintype "bidirectional"))
    )
    (net (code "13") (name "/PA9") (class "Default")
      (node (ref "BOOTLOAD") (pin "5") (pinfunction "5_5") (pintype "passive"))
      (node (ref "U$1") (pin "101") (pinfunction "PA9_101") (pintype "bidirectional"))
    )
    (net (code "14") (name "/PA10") (class "Default")
      (node (ref "BOOTLOAD") (pin "4") (pinfunction "4_4") (pintype "passive"))
      (node (ref "SV3") (pin "3") (pinfunction "3_3") (pintype "passive"))
      (node (ref "U$1") (pin "102") (pinfunction "PA10_102") (pintype "bidirectional"))
    )
    (net (code "15") (name "/PA11") (class "Default")
      (node (ref "U$1") (pin "103") (pinfunction "PA11_103") (pintype "bidirectional"))
    )
    (net (code "16") (name "/PA12") (class "Default")
      (node (ref "U$1") (pin "104") (pinfunction "PA12_104") (pintype "bidirectional"))
    )
    (net (code "17") (name "/PA13") (class "Default")
      (node (ref "ST-LINK1") (pin "4") (pinfunction "4_4") (pintype "passive"))
      (node (ref "U$1") (pin "105") (pinfunction "PA13_105") (pintype "bidirectional"))
    )
    (net (code "18") (name "/PA14") (class "Default")
      (node (ref "ST-LINK1") (pin "2") (pinfunction "2_2") (pintype "passive"))
      (node (ref "U$1") (pin "109") (pinfunction "PA14_109") (pintype "bidirectional"))
    )
    (net (code "19") (name "/PA15") (class "Default")
      (node (ref "U$1") (pin "110") (pinfunction "PA15_110") (pintype "bidirectional"))
      (node (ref "U$2") (pin "2") (pinfunction "MPPSET_2_2") (pintype "bidirectional"))
    )
    (net (code "20") (name "/PB0") (class "Default")
      (node (ref "U$1") (pin "46") (pinfunction "PB0_46") (pintype "bidirectional"))
    )
    (net (code "21") (name "/PB1") (class "Default")
      (node (ref "U$1") (pin "47") (pinfunction "PB1_47") (pintype "bidirectional"))
    )
    (net (code "22") (name "/PB2") (class "Default")
      (node (ref "R7") (pin "2") (pinfunction "2_2") (pintype "passive"))
      (node (ref "U$1") (pin "48") (pinfunction "PB2_48") (pintype "bidirectional"))
    )
    (net (code "23") (name "/PB3") (class "Default")
      (node (ref "U$1") (pin "133") (pinfunction "PB3_133") (pintype "bidirectional"))
    )
    (net (code "24") (name "/PB4") (class "Default")
      (node (ref "U$1") (pin "134") (pinfunction "PB4_134") (pintype "bidirectional"))
      (node (ref "U$2") (pin "6") (pinfunction "VREF_6_6") (pintype "bidirectional"))
    )
    (net (code "25") (name "/PB5") (class "Default")
      (node (ref "U$1") (pin "135") (pinfunction "PB5_135") (pintype "bidirectional"))
    )
    (net (code "26") (name "/PB6") (class "Default")
      (node (ref "U$1") (pin "136") (pinfunction "PB6_136") (pintype "bidirectional"))
    )
    (net (code "27") (name "/PB7") (class "Default")
      (node (ref "U$1") (pin "137") (pinfunction "PB7_137") (pintype "bidirectional"))
    )
    (net (code "28") (name "/PB8") (class "Default")
      (node (ref "SV3") (pin "15") (pinfunction "15_15") (pintype "passive"))
      (node (ref "U$1") (pin "139") (pinfunction "PB8_139") (pintype "bidirectional"))
    )
    (net (code "29") (name "/PB9") (class "Default")
      (node (ref "SV3") (pin "16") (pinfunction "16_16") (pintype "passive"))
      (node (ref "U$1") (pin "140") (pinfunction "PB9_140") (pintype "bidirectional"))
    )
    (net (code "30") (name "/PB10") (class "Default")
      (node (ref "U$1") (pin "69") (pinfunction "PB10_69") (pintype "bidirectional"))
      (node (ref "U4") (pin "43") (pinfunction "SCL_43") (pintype "input"))
    )
    (net (code "31") (name "/PB11") (class "Default")
      (node (ref "U$1") (pin "70") (pinfunction "PB11_70") (pintype "bidirectional"))
      (node (ref "U4") (pin "44") (pinfunction "SDA_44") (pintype "passive"))
    )
    (net (code "32") (name "/PB12") (class "Default")
      (node (ref "U$1") (pin "73") (pinfunction "PB12_73") (pintype "bidirectional"))
      (node (ref "U4") (pin "28") (pinfunction "OUT_CLK/DATA_REQ_28") (pintype "input"))
    )
    (net (code "33") (name "/PB13") (class "Default")
      (node (ref "U$1") (pin "74") (pinfunction "PB13_74") (pintype "bidirectional"))
      (node (ref "U4") (pin "45") (pinfunction "SCKR_45") (pintype "input"))
    )
    (net (code "34") (name "/PB14") (class "Default")
      (node (ref "U$1") (pin "75") (pinfunction "PB14_75") (pintype "bidirectional"))
      (node (ref "U4") (pin "30") (pinfunction "RESET_30") (pintype "input"))
    )
    (net (code "35") (name "/PB15") (class "Default")
      (node (ref "U$1") (pin "76") (pinfunction "PB15_76") (pintype "bidirectional"))
    )
    (net (code "36") (name "/PC0") (class "Default")
      (node (ref "U$1") (pin "26") (pinfunction "PC0_26") (pintype "bidirectional"))
    )
    (net (code "37") (name "/PC1") (class "Default")
      (node (ref "U$1") (pin "27") (pinfunction "PC1_27") (pintype "bidirectional"))
      (node (ref "U4") (pin "46") (pinfunction "SDI_46") (pintype "input"))
    )
    (net (code "38") (name "/PC2") (class "Default")
      (node (ref "U$1") (pin "28") (pinfunction "PC2_28") (pintype "bidirectional"))
    )
    (net (code "39") (name "/PC3") (class "Default")
      (node (ref "U$1") (pin "29") (pinfunction "PC3_29") (pintype "bidirectional"))
    )
    (net (code "40") (name "/PC4") (class "Default")
      (node (ref "U$1") (pin "44") (pinfunction "PC4_44") (pintype "bidirectional"))
      (node (ref "U$2") (pin "1") (pinfunction "VCC_1_1") (pintype "bidirectional"))
    )
    (net (code "41") (name "/PC5") (class "Default")
      (node (ref "U$1") (pin "45") (pinfunction "PC5_45") (pintype "bidirectional"))
      (node (ref "U$2") (pin "7") (pinfunction "TERMEN_7_7") (pintype "bidirectional"))
    )
    (net (code "42") (name "/PC6") (class "Default")
      (node (ref "SV3") (pin "4") (pinfunction "4_4") (pintype "passive"))
      (node (ref "U$1") (pin "96") (pinfunction "PC6_96") (pintype "bidirectional"))
    )
    (net (code "43") (name "/PC7") (class "Default")
      (node (ref "U$1") (pin "97") (pinfunction "PC7_97") (pintype "bidirectional"))
    )
    (net (code "44") (name "/PC8") (class "Default")
      (node (ref "JP2") (pin "6") (pinfunction "6_6") (pintype "passive"))
      (node (ref "U$1") (pin "98") (pinfunction "PC8_98") (pintype "bidirectional"))
      (node (ref "U5") (pin "7") (pinfunction "DO_7") (pintype "bidirectional"))
    )
    (net (code "45") (name "/PC9") (class "Default")
      (node (ref "U$1") (pin "99") (pinfunction "PC9_99") (pintype "bidirectional"))
    )
    (net (code "46") (name "/PC10") (class "Default")
      (node (ref "U$1") (pin "111") (pinfunction "PC10_111") (pintype "bidirectional"))
    )
    (net (code "47") (name "/PC11") (class "Default")
      (node (ref "U$1") (pin "112") (pinfunction "PC11_112") (pintype "bidirectional"))
    )
    (net (code "48") (name "/PC12") (class "Default")
      (node (ref "JP2") (pin "3") (pinfunction "3_3") (pintype "passive"))
      (node (ref "U$1") (pin "113") (pinfunction "PC12_113") (pintype "bidirectional"))
      (node (ref "U5") (pin "4") (pinfunction "VCC_4") (pintype "bidirectional"))
    )
    (net (code "49") (name "/PC13") (class "Default")
      (node (ref "LED7") (pin "A") (pinfunction "A_A") (pintype "passive"))
      (node (ref "SV3") (pin "1") (pinfunction "1_1") (pintype "passive"))
      (node (ref "U$1") (pin "7") (pinfunction "PC13_7") (pintype "bidirectional"))
    )
    (net (code "50") (name "/PD0") (class "Default")
      (node (ref "U$1") (pin "114") (pinfunction "PD0_114") (pintype "bidirectional"))
    )
    (net (code "51") (name "/PD1") (class "Default")
      (node (ref "FET1") (pin "1") (pinfunction "G_1") (pintype "passive"))
      (node (ref "U$1") (pin "115") (pinfunction "PD1_115") (pintype "bidirectional"))
    )
    (net (code "52") (name "/PD2") (class "Default")
      (node (ref "JP2") (pin "2") (pinfunction "2_2") (pintype "passive"))
      (node (ref "U$1") (pin "116") (pinfunction "PD2_116") (pintype "bidirectional"))
      (node (ref "U5") (pin "3") (pinfunction "DI_3") (pintype "bidirectional"))
    )
    (net (code "53") (name "/PD3") (class "Default")
      (node (ref "SV3") (pin "7") (pinfunction "7_7") (pintype "passive"))
      (node (ref "U$1") (pin "117") (pinfunction "PD3_117") (pintype "bidirectional"))
    )
    (net (code "54") (name "/PD4") (class "Default")
      (node (ref "U$1") (pin "118") (pinfunction "PD4_118") (pintype "bidirectional"))
    )
    (net (code "55") (name "/PD5") (class "Default")
      (node (ref "U$1") (pin "119") (pinfunction "PD5_119") (pintype "bidirectional"))
    )
    (net (code "56") (name "/PD6") (class "Default")
      (node (ref "R35") (pin "1") (pinfunction "1_1") (pintype "passive"))
      (node (ref "S2") (pin "2") (pinfunction "2_2") (pintype "passive"))
      (node (ref "U$1") (pin "122") (pinfunction "PD6_122") (pintype "bidirectional"))
    )
    (net (code "57") (name "/PD7") (class "Default")
      (node (ref "R36") (pin "1") (pinfunction "1_1") (pintype "passive"))
      (node (ref "S3") (pin "2") (pinfunction "2_2") (pintype "passive"))
      (node (ref "U$1") (pin "123") (pinfunction "PD7_123") (pintype "bidirectional"))
    )
    (net (code "58") (name "/PD8") (class "Default")
      (node (ref "U$1") (pin "77") (pinfunction "PD8_77") (pintype "bidirectional"))
      (node (ref "USART3/FTDI") (pin "5") (pinfunction "5_5") (pintype "passive"))
    )
    (net (code "59") (name "/PD9") (class "Default")
      (node (ref "U$1") (pin "78") (pinfunction "PD9_78") (pintype "bidirectional"))
      (node (ref "USART3/FTDI") (pin "4") (pinfunction "4_4") (pintype "passive"))
    )
    (net (code "60") (name "/PD10") (class "Default")
      (node (ref "U$1") (pin "79") (pinfunction "PD10_79") (pintype "bidirectional"))
    )
    (net (code "61") (name "/PD11") (class "Default")
      (node (ref "R39") (pin "2") (pinfunction "2_2") (pintype "passive"))
      (node (ref "S6") (pin "2") (pinfunction "2_2") (pintype "passive"))
      (node (ref "U$1") (pin "80") (pinfunction "PD11_80") (pintype "bidirectional"))
    )
    (net (code "62") (name "/PD12") (class "Default")
      (node (ref "R40") (pin "2") (pinfunction "2_2") (pintype "passive"))
      (node (ref "S7") (pin "2") (pinfunction "2_2") (pintype "passive"))
      (node (ref "U$1") (pin "81") (pinfunction "PD12_81") (pintype "bidirectional"))
    )
    (net (code "63") (name "/PD13") (class "Default")
      (node (ref "U$1") (pin "82") (pinfunction "PD13_82") (pintype "bidirectional"))
    )
    (net (code "64") (name "/PD14") (class "Default")
      (node (ref "U$1") (pin "85") (pinfunction "PD14_85") (pintype "bidirectional"))
    )
    (net (code "65") (name "/PD15") (class "Default")
      (node (ref "U$1") (pin "86") (pinfunction "PD15_86") (pintype "bidirectional"))
    )
    (net (code "66") (name "/PDR_ON") (class "Default")
      (node (ref "U$1") (pin "143") (pinfunction "PDR_ON_143") (pintype "bidirectional"))
    )
    (net (code "67") (name "/PE0") (class "Default")
      (node (ref "U$1") (pin "141") (pinfunction "PE0\\_141") (pintype "bidirectional"))
    )
    (net (code "68") (name "/PE1") (class "Default")
      (node (ref "U$1") (pin "142") (pinfunction "PE1_142") (pintype "bidirectional"))
    )
    (net (code "69") (name "/PE2") (class "Default")
      (node (ref "U$1") (pin "1") (pinfunction "PE2_1") (pintype "bidirectional"))
    )
    (net (code "70") (name "/PE3") (class "Default")
      (node (ref "SV3") (pin "2") (pinfunction "2_2") (pintype "passive"))
      (node (ref "U$1") (pin "2") (pinfunction "PE3_2") (pintype "bidirectional"))
    )
    (net (code "71") (name "/PE4") (class "Default")
      (node (ref "SV3") (pin "8") (pinfunction "8_8") (pintype "passive"))
      (node (ref "U$1") (pin "3") (pinfunction "PE4_3") (pintype "bidirectional"))
    )
    (net (code "72") (name "/PE5") (class "Default")
      (node (ref "SV3") (pin "10") (pinfunction "10_10") (pintype "passive"))
      (node (ref "U$1") (pin "4") (pinfunction "PE5_4") (pintype "bidirectional"))
    )
    (net (code "73") (name "/PE6") (class "Default")
      (node (ref "SV3") (pin "9") (pinfunction "9_9") (pintype "passive"))
      (node (ref "U$1") (pin "5") (pinfunction "PE6_5") (pintype "bidirectional"))
    )
    (net (code "74") (name "/PE7") (class "Default")
      (node (ref "U$1") (pin "58") (pinfunction "PE7_58") (pintype "bidirectional"))
    )
    (net (code "75") (name "/PE8") (class "Default")
      (node (ref "U$1") (pin "59") (pinfunction "PE8_59") (pintype "bidirectional"))
    )
    (net (code "76") (name "/PE9") (class "Default")
      (node (ref "U$1") (pin "60") (pinfunction "PE9_60") (pintype "bidirectional"))
    )
    (net (code "77") (name "/PE10") (class "Default")
      (node (ref "U$1") (pin "63") (pinfunction "PE10_63") (pintype "bidirectional"))
    )
    (net (code "78") (name "/PE11") (class "Default")
      (node (ref "U$1") (pin "64") (pinfunction "PE11_64") (pintype "bidirectional"))
    )
    (net (code "79") (name "/PE12") (class "Default")
      (node (ref "U$1") (pin "65") (pinfunction "PE12_65") (pintype "bidirectional"))
    )
    (net (code "80") (name "/PE13") (class "Default")
      (node (ref "U$1") (pin "66") (pinfunction "PE13_66") (pintype "bidirectional"))
    )
    (net (code "81") (name "/PE14") (class "Default")
      (node (ref "U$1") (pin "67") (pinfunction "PE14_67") (pintype "bidirectional"))
    )
    (net (code "82") (name "/PE15") (class "Default")
      (node (ref "U$1") (pin "68") (pinfunction "PE15_68") (pintype "bidirectional"))
    )
    (net (code "83") (name "/PF0") (class "Default")
      (node (ref "U$1") (pin "10") (pinfunction "PF0_10") (pintype "bidirectional"))
    )
    (net (code "84") (name "/PF1") (class "Default")
      (node (ref "U$1") (pin "11") (pinfunction "PF1_11") (pintype "bidirectional"))
    )
    (net (code "85") (name "/PF2") (class "Default")
      (node (ref "U$1") (pin "12") (pinfunction "PF2_12") (pintype "bidirectional"))
    )
    (net (code "86") (name "/PF3") (class "Default")
      (node (ref "U$1") (pin "13") (pinfunction "PF3_13") (pintype "bidirectional"))
    )
    (net (code "87") (name "/PF4") (class "Default")
      (node (ref "U$1") (pin "14") (pinfunction "PF4_14") (pintype "bidirectional"))
    )
    (net (code "88") (name "/PF5") (class "Default")
      (node (ref "U$1") (pin "15") (pinfunction "PF5_15") (pintype "bidirectional"))
    )
    (net (code "89") (name "/PF6") (class "Default")
      (node (ref "SV1") (pin "3") (pinfunction "3_3") (pintype "passive"))
      (node (ref "U$1") (pin "18") (pinfunction "PF6_18") (pintype "bidirectional"))
    )
    (net (code "90") (name "/PF7") (class "Default")
      (node (ref "SV1") (pin "4") (pinfunction "4_4") (pintype "passive"))
      (node (ref "U$1") (pin "19") (pinfunction "PF7_19") (pintype "bidirectional"))
    )
    (net (code "91") (name "/PF8") (class "Default")
      (node (ref "U$1") (pin "20") (pinfunction "PF8_20") (pintype "bidirectional"))
    )
    (net (code "92") (name "/PF9") (class "Default")
      (node (ref "U$1") (pin "21") (pinfunction "PF9_21") (pintype "bidirectional"))
    )
    (net (code "93") (name "/PF10") (class "Default")
      (node (ref "R41") (pin "2") (pinfunction "2_2") (pintype "passive"))
      (node (ref "S8") (pin "2") (pinfunction "2_2") (pintype "passive"))
      (node (ref "U$1") (pin "22") (pinfunction "PF10_22") (pintype "bidirectional"))
    )
    (net (code "94") (name "/PF11") (class "Default")
      (node (ref "U$1") (pin "49") (pinfunction "PF11_49") (pintype "bidirectional"))
    )
    (net (code "95") (name "/PF12") (class "Default")
      (node (ref "U$1") (pin "50") (pinfunction "PF12_50") (pintype "bidirectional"))
    )
    (net (code "96") (name "/PF13") (class "Default")
      (node (ref "U$1") (pin "53") (pinfunction "PF13_53") (pintype "bidirectional"))
    )
    (net (code "97") (name "/PF14") (class "Default")
      (node (ref "U$1") (pin "54") (pinfunction "PF14_54") (pintype "bidirectional"))
    )
    (net (code "98") (name "/PF15") (class "Default")
      (node (ref "U$1") (pin "55") (pinfunction "PF15_55") (pintype "bidirectional"))
    )
    (net (code "99") (name "/PG0") (class "Default")
      (node (ref "U$1") (pin "56") (pinfunction "PG0_56") (pintype "bidirectional"))
    )
    (net (code "100") (name "/PG1") (class "Default")
      (node (ref "U$1") (pin "57") (pinfunction "PG1_57") (pintype "bidirectional"))
    )
    (net (code "101") (name "/PG2") (class "Default")
      (node (ref "R37") (pin "1") (pinfunction "1_1") (pintype "passive"))
      (node (ref "S4") (pin "2") (pinfunction "2_2") (pintype "passive"))
      (node (ref "U$1") (pin "87") (pinfunction "PG2_87") (pintype "bidirectional"))
    )
    (net (code "102") (name "/PG3") (class "Default")
      (node (ref "R38") (pin "2") (pinfunction "2_2") (pintype "passive"))
      (node (ref "S5") (pin "2") (pinfunction "2_2") (pintype "passive"))
      (node (ref "U$1") (pin "88") (pinfunction "PG3_88") (pintype "bidirectional"))
    )
    (net (code "103") (name "/PG4") (class "Default")
      (node (ref "U$1") (pin "89") (pinfunction "PG4_89") (pintype "bidirectional"))
    )
    (net (code "104") (name "/PG5") (class "Default")
      (node (ref "U$1") (pin "90") (pinfunction "PG5_90") (pintype "bidirectional"))
    )
    (net (code "105") (name "/PG6") (class "Default")
      (node (ref "U$1") (pin "91") (pinfunction "PG6_91") (pintype "bidirectional"))
    )
    (net (code "106") (name "/PG7") (class "Default")
      (node (ref "R34") (pin "1") (pinfunction "1_1") (pintype "passive"))
      (node (ref "S1") (pin "2") (pinfunction "2_2") (pintype "passive"))
      (node (ref "U$1") (pin "92") (pinfunction "PG7_92") (pintype "bidirectional"))
    )
    (net (code "107") (name "/PG8") (class "Default")
      (node (ref "U$1") (pin "93") (pinfunction "PG8_93") (pintype "bidirectional"))
    )
    (net (code "108") (name "/PG9") (class "Default")
      (node (ref "SV3") (pin "13") (pinfunction "13_13") (pintype "passive"))
      (node (ref "U$1") (pin "124") (pinfunction "PG9_124") (pintype "bidirectional"))
    )
    (net (code "109") (name "/PG10") (class "Default")
      (node (ref "SV3") (pin "6") (pinfunction "6_6") (pintype "passive"))
      (node (ref "U$1") (pin "125") (pinfunction "PG10_125") (pintype "bidirectional"))
    )
    (net (code "110") (name "/PG11") (class "Default")
      (node (ref "SV3") (pin "5") (pinfunction "5_5") (pintype "passive"))
      (node (ref "U$1") (pin "126") (pinfunction "PG11_126") (pintype "bidirectional"))
    )
    (net (code "111") (name "/PG12") (class "Default")
      (node (ref "U$1") (pin "127") (pinfunction "PG12_127") (pintype "bidirectional"))
    )
    (net (code "112") (name "/PG13") (class "Default")
      (node (ref "U$1") (pin "128") (pinfunction "PG13_128") (pintype "bidirectional"))
    )
    (net (code "113") (name "/PG14") (class "Default")
      (node (ref "U$1") (pin "129") (pinfunction "PG14_129") (pintype "bidirectional"))
    )
    (net (code "114") (name "/PG15") (class "Default")
      (node (ref "U$1") (pin "132") (pinfunction "PG15_132") (pintype "bidirectional"))
    )
    (net (code "115") (name "/PH0") (class "Default")
      (node (ref "C21") (pin "1") (pinfunction "1_1") (pintype "passive"))
      (node (ref "U$1") (pin "23") (pinfunction "PH0_23") (pintype "bidirectional"))
      (node (ref "XTAL1") (pin "2") (pinfunction "2_2") (pintype "passive"))
    )
    (net (code "116") (name "/PH1") (class "Default")
      (node (ref "C20") (pin "1") (pinfunction "1_1") (pintype "passive"))
      (node (ref "U$1") (pin "24") (pinfunction "PH1_24") (pintype "bidirectional"))
      (node (ref "XTAL1") (pin "1") (pinfunction "1_1") (pintype "passive"))
    )
    (net (code "117") (name "/VBAT") (class "Default")
      (node (ref "C1") (pin "1") (pinfunction "1_1") (pintype "passive"))
      (node (ref "R8") (pin "1") (pinfunction "1_1") (pintype "passive"))
      (node (ref "U$1") (pin "6") (pinfunction "VBAT_6") (pintype "bidirectional"))
    )
    (net (code "118") (name "/VCAP_1") (class "Default")
      (node (ref "C4") (pin "1") (pinfunction "1_1") (pintype "passive"))
      (node (ref "U$1") (pin "71") (pinfunction "VCAP_1_71") (pintype "bidirectional"))
    )
    (net (code "119") (name "/VCAP_2") (class "Default")
      (node (ref "C5") (pin "1") (pinfunction "1_1") (pintype "passive"))
      (node (ref "U$1") (pin "106") (pinfunction "VCAP_2_106") (pintype "bidirectional"))
    )
    (net (code "120") (name "/VDDA") (class "Default")
      (node (ref "C13") (pin "1") (pinfunction "1_1") (pintype "passive"))
      (node (ref "C14") (pin "1") (pinfunction "1_1") (pintype "passive"))
      (node (ref "L2") (pin "2") (pinfunction "2_2") (pintype "passive"))
      (node (ref "R2") (pin "2") (pinfunction "2_2") (pintype "passive"))
      (node (ref "U$1") (pin "33") (pinfunction "VDDA_33") (pintype "bidirectional"))
    )
    (net (code "121") (name "/VDDUSB") (class "Default")
      (node (ref "U$1") (pin "95") (pinfunction "VDDUSB_95") (pintype "bidirectional"))
    )
    (net (code "122") (name "/VREF") (class "Default")
      (node (ref "C15") (pin "1") (pinfunction "1_1") (pintype "passive"))
      (node (ref "C16") (pin "1") (pinfunction "1_1") (pintype "passive"))
      (node (ref "R2") (pin "1") (pinfunction "1_1") (pintype "passive"))
      (node (ref "U$1") (pin "32") (pinfunction "VREF+_32") (pintype "bidirectional"))
    )
    (net (code "123") (name "3.3V") (class "Default")
      (node (ref "BOOT") (pin "P$2") (pinfunction "2_P$2") (pintype "passive"))
      (node (ref "C10") (pin "1") (pinfunction "1_1") (pintype "passive"))
      (node (ref "C11") (pin "1") (pinfunction "1_1") (pintype "passive"))
      (node (ref "C12") (pin "1") (pinfunction "1_1") (pintype "passive"))
      (node (ref "C17") (pin "2") (pinfunction "2_2") (pintype "passive"))
      (node (ref "C27") (pin "2") (pinfunction "2_2") (pintype "passive"))
      (node (ref "C28") (pin "2") (pinfunction "2_2") (pintype "passive"))
      (node (ref "C29") (pin "2") (pinfunction "2_2") (pintype "passive"))
      (node (ref "C30") (pin "1") (pinfunction "1_1") (pintype "passive"))
      (node (ref "C6") (pin "1") (pinfunction "1_1") (pintype "passive"))
      (node (ref "C7") (pin "1") (pinfunction "1_1") (pintype "passive"))
      (node (ref "C8") (pin "1") (pinfunction "1_1") (pintype "passive"))
      (node (ref "C9") (pin "1") (pinfunction "1_1") (pintype "passive"))
      (node (ref "D4") (pin "1") (pinfunction "A_1") (pintype "passive"))
      (node (ref "FET1") (pin "2") (pinfunction "S_2") (pintype "passive"))
      (node (ref "JP5") (pin "2") (pinfunction "2_2") (pintype "passive"))
      (node (ref "L2") (pin "1") (pinfunction "1_1") (pintype "passive"))
      (node (ref "MICROPHONE") (pin "1") (pinfunction "1_1") (pintype "passive"))
      (node (ref "R5") (pin "2") (pinfunction "2_2") (pintype "passive"))
      (node (ref "R6") (pin "2") (pinfunction "2_2") (pintype "passive"))
      (node (ref "R9") (pin "2") (pinfunction "2_2") (pintype "passive"))
      (node (ref "RI5") (pin "1") (pinfunction "1_1") (pintype "passive"))
      (node (ref "S1") (pin "4") (pinfunction "4_4") (pintype "passive"))
      (node (ref "S2") (pin "4") (pinfunction "4_4") (pintype "passive"))
      (node (ref "S3") (pin "4") (pinfunction "4_4") (pintype "passive"))
      (node (ref "S4") (pin "4") (pinfunction "4_4") (pintype "passive"))
      (node (ref "S5") (pin "4") (pinfunction "4_4") (pintype "passive"))
      (node (ref "S6") (pin "4") (pinfunction "4_4") (pintype "passive"))
      (node (ref "S7") (pin "4") (pinfunction "4_4") (pintype "passive"))
      (node (ref "S8") (pin "4") (pinfunction "4_4") (pintype "passive"))
      (node (ref "ST-LINK1") (pin "1") (pinfunction "1_1") (pintype "passive"))
      (node (ref "SV1") (pin "5") (pinfunction "5_5") (pintype "passive"))
      (node (ref "SV3") (pin "17") (pinfunction "17_17") (pintype "passive"))
      (node (ref "U$1") (pin "108") (pinfunction "VDD_108") (pintype "bidirectional"))
      (node (ref "U$1") (pin "121") (pinfunction "VDD_121") (pintype "bidirectional"))
      (node (ref "U$1") (pin "131") (pinfunction "VDD_131") (pintype "bidirectional"))
      (node (ref "U$1") (pin "144") (pinfunction "VDD_144") (pintype "bidirectional"))
      (node (ref "U$1") (pin "17") (pinfunction "VDD_17") (pintype "bidirectional"))
      (node (ref "U$1") (pin "30") (pinfunction "VDD_30") (pintype "bidirectional"))
      (node (ref "U$1") (pin "39") (pinfunction "VDD_39") (pintype "bidirectional"))
      (node (ref "U$1") (pin "52") (pinfunction "VDD_52") (pintype "bidirectional"))
      (node (ref "U$1") (pin "62") (pinfunction "VDD_62") (pintype "bidirectional"))
      (node (ref "U$1") (pin "72") (pinfunction "VDD_72") (pintype "bidirectional"))
      (node (ref "U$1") (pin "84") (pinfunction "VDD_84") (pintype "bidirectional"))
      (node (ref "U$2") (pin "15") (pinfunction "HIDRV_15_15") (pintype "bidirectional"))
      (node (ref "U1") (pin "20") (pinfunction "VDD_20") (pintype "bidirectional"))
      (node (ref "U4") (pin "31") (pinfunction "VDD_4_31") (pintype "output"))
      (node (ref "U4") (pin "32") (pinfunction "TESTEN_32") (pintype "output"))
      (node (ref "U4") (pin "34") (pinfunction "VDD_1_34") (pintype "input"))
      (node (ref "U4") (pin "42") (pinfunction "VDD_3_42") (pintype "bidirectional"))
      (node (ref "U4") (pin "47") (pinfunction "SRC_INT_47") (pintype "power_in"))
      (node (ref "U4") (pin "48") (pinfunction "BIT_EN_48") (pintype "bidirectional"))
      (node (ref "U4") (pin "53") (pinfunction "VDD_2_53") (pintype "output"))
    )
    (net (code "124") (name "AIC0") (class "Default")
      (node (ref "U1") (pin "3") (pinfunction "AIC0_3") (pintype "bidirectional"))
    )
    (net (code "125") (name "GND") (class "Default")
      (node (ref "BOOTLOAD") (pin "1") (pinfunction "1_1") (pintype "passive"))
      (node (ref "C1") (pin "2") (pinfunction "2_2") (pintype "passive"))
      (node (ref "C10") (pin "2") (pinfunction "2_2") (pintype "passive"))
      (node (ref "C11") (pin "2") (pinfunction "2_2") (pintype "passive"))
      (node (ref "C12") (pin "2") (pinfunction "2_2") (pintype "passive"))
      (node (ref "C13") (pin "2") (pinfunction "2_2") (pintype "passive"))
      (node (ref "C14") (pin "2") (pinfunction "2_2") (pintype "passive"))
      (node (ref "C15") (pin "2") (pinfunction "2_2") (pintype "passive"))
      (node (ref "C16") (pin "2") (pinfunction "2_2") (pintype "passive"))
      (node (ref "C17") (pin "1") (pinfunction "1_1") (pintype "passive"))
      (node (ref "C18") (pin "2") (pinfunction "2_2") (pintype "passive"))
      (node (ref "C19") (pin "2") (pinfunction "2_2") (pintype "passive"))
      (node (ref "C2") (pin "2") (pinfunction "2_2") (pintype "passive"))
      (node (ref "C20") (pin "2") (pinfunction "2_2") (pintype "passive"))
      (node (ref "C21") (pin "2") (pinfunction "2_2") (pintype "passive"))
      (node (ref "C23") (pin "2") (pinfunction "2_2") (pintype "passive"))
      (node (ref "C24") (pin "2") (pinfunction "2_2") (pintype "passive"))
      (node (ref "C25") (pin "2") (pinfunction "2_2") (pintype "passive"))
      (node (ref "C26") (pin "2") (pinfunction "2_2") (pintype "passive"))
      (node (ref "C27") (pin "1") (pinfunction "1_1") (pintype "passive"))
      (node (ref "C27_1812") (pin "2") (pinfunction "2_2") (pintype "passive"))
      (node (ref "C28") (pin "1") (pinfunction "1_1") (pintype "passive"))
      (node (ref "C29") (pin "1") (pinfunction "1_1") (pintype "passive"))
      (node (ref "C3") (pin "2") (pinfunction "2_2") (pintype "passive"))
      (node (ref "C30") (pin "2") (pinfunction "2_2") (pintype "passive"))
      (node (ref "C31") (pin "2") (pinfunction "2_2") (pintype "passive"))
      (node (ref "C32") (pin "2") (pinfunction "2_2") (pintype "passive"))
      (node (ref "C33") (pin "2") (pinfunction "2_2") (pintype "passive"))
      (node (ref "C34") (pin "-") (pinfunction "-_-") (pintype "passive"))
      (node (ref "C35") (pin "-") (pinfunction "-_-") (pintype "passive"))
      (node (ref "C36") (pin "2") (pinfunction "2_2") (pintype "passive"))
      (node (ref "C37") (pin "2") (pinfunction "2_2") (pintype "passive"))
      (node (ref "C38") (pin "2") (pinfunction "2_2") (pintype "passive"))
      (node (ref "C39") (pin "2") (pinfunction "2_2") (pintype "passive"))
      (node (ref "C4") (pin "2") (pinfunction "2_2") (pintype "passive"))
      (node (ref "C5") (pin "2") (pinfunction "2_2") (pintype "passive"))
      (node (ref "C6") (pin "2") (pinfunction "2_2") (pintype "passive"))
      (node (ref "C7") (pin "2") (pinfunction "2_2") (pintype "passive"))
      (node (ref "C8") (pin "2") (pinfunction "2_2") (pintype "passive"))
      (node (ref "C9") (pin "2") (pinfunction "2_2") (pintype "passive"))
      (node (ref "CC") (pin "2") (pinfunction "2_2") (pintype "passive"))
      (node (ref "CC1") (pin "2") (pinfunction "2_2") (pintype "passive"))
      (node (ref "CIN") (pin "2") (pinfunction "2_2") (pintype "passive"))
      (node (ref "COUT") (pin "2") (pinfunction "2_2") (pintype "passive"))
      (node (ref "CTTC") (pin "2") (pinfunction "2_2") (pintype "passive"))
      (node (ref "CTTC1") (pin "2") (pinfunction "2_2") (pintype "passive"))
      (node (ref "CTTC2") (pin "2") (pinfunction "2_2") (pintype "passive"))
      (node (ref "CTTC3") (pin "2") (pinfunction "2_2") (pintype "passive"))
      (node (ref "CTTC4") (pin "2") (pinfunction "2_2") (pintype "passive"))
      (node (ref "CTTC5") (pin "2") (pinfunction "2_2") (pintype "passive"))
      (node (ref "D6") (pin "A") (pinfunction "A_A") (pintype "passive"))
      (node (ref "IC8") (pin "10") (pinfunction "VSS_10") (pintype "power_in"))
      (node (ref "IC8") (pin "16") (pinfunction "~{CE}_16") (pintype "input"))
      (node (ref "IC8") (pin "17") (pinfunction "PGND_17") (pintype "input"))
      (node (ref "IC8") (pin "18") (pinfunction "PGND_18") (pintype "input"))
      (node (ref "J1") (pin "1") (pinfunction "1_1") (pintype "passive"))
      (node (ref "J2") (pin "1") (pinfunction "1_1") (pintype "passive"))
      (node (ref "MICROPHONE") (pin "2") (pinfunction "2_2") (pintype "passive"))
      (node (ref "R1") (pin "1") (pinfunction "1_1") (pintype "passive"))
      (node (ref "R16") (pin "1") (pinfunction "1_1") (pintype "passive"))
      (node (ref "R17") (pin "1") (pinfunction "1_1") (pintype "passive"))
      (node (ref "R20") (pin "1") (pinfunction "1_1") (pintype "passive"))
      (node (ref "R23") (pin "1") (pinfunction "1_1") (pintype "passive"))
      (node (ref "R24") (pin "1") (pinfunction "1_1") (pintype "passive"))
      (node (ref "R27") (pin "1") (pinfunction "1_1") (pintype "passive"))
      (node (ref "R28") (pin "1") (pinfunction "1_1") (pintype "passive"))
      (node (ref "R29") (pin "1") (pinfunction "1_1") (pintype "passive"))
      (node (ref "R31") (pin "1") (pinfunction "1_1") (pintype "passive"))
      (node (ref "R34") (pin "2") (pinfunction "2_2") (pintype "passive"))
      (node (ref "R35") (pin "2") (pinfunction "2_2") (pintype "passive"))
      (node (ref "R36") (pin "2") (pinfunction "2_2") (pintype "passive"))
      (node (ref "R37") (pin "2") (pinfunction "2_2") (pintype "passive"))
      (node (ref "R38") (pin "1") (pinfunction "1_1") (pintype "passive"))
      (node (ref "R39") (pin "1") (pinfunction "1_1") (pintype "passive"))
      (node (ref "R4") (pin "1") (pinfunction "1_1") (pintype "passive"))
      (node (ref "R40") (pin "1") (pinfunction "1_1") (pintype "passive"))
      (node (ref "R41") (pin "1") (pinfunction "1_1") (pintype "passive"))
      (node (ref "R7") (pin "1") (pinfunction "1_1") (pintype "passive"))
      (node (ref "RESET") (pin "P$1") (pinfunction "1_P$1") (pintype "passive"))
      (node (ref "RI1") (pin "2") (pinfunction "2_2") (pintype "passive"))
      (node (ref "RI2") (pin "2") (pinfunction "2_2") (pintype "passive"))
      (node (ref "RI4") (pin "2") (pinfunction "2_2") (pintype "passive"))
      (node (ref "RT2") (pin "1") (pinfunction "1_1") (pintype "passive"))
      (node (ref "RTHERMAL") (pin "2") (pinfunction "2_2") (pintype "passive"))
      (node (ref "ST-LINK1") (pin "3") (pinfunction "3_3") (pintype "passive"))
      (node (ref "SV1") (pin "1") (pinfunction "1_1") (pintype "passive"))
      (node (ref "SV1") (pin "2") (pinfunction "2_2") (pintype "passive"))
      (node (ref "SV2") (pin "2") (pinfunction "2_2") (pintype "passive"))
      (node (ref "SV3") (pin "18") (pinfunction "18_18") (pintype "passive"))
      (node (ref "TPS61028") (pin "10") (pinfunction "10_10") (pintype "passive"))
      (node (ref "TPS61028") (pin "5") (pinfunction "5_5") (pintype "passive"))
      (node (ref "TPS61028") (pin "8") (pinfunction "8_8") (pintype "passive"))
      (node (ref "TPS63031") (pin "3") (pinfunction "3_3") (pintype "passive"))
      (node (ref "TPS63031") (pin "9") (pinfunction "9_9") (pintype "passive"))
      (node (ref "U$1") (pin "107") (pinfunction "VSS_107") (pintype "bidirectional"))
      (node (ref "U$1") (pin "120") (pinfunction "VSS_120") (pintype "bidirectional"))
      (node (ref "U$1") (pin "130") (pinfunction "VSS_130") (pintype "bidirectional"))
      (node (ref "U$1") (pin "16") (pinfunction "VSS_16") (pintype "bidirectional"))
      (node (ref "U$1") (pin "31") (pinfunction "VSSA_31") (pintype "bidirectional"))
      (node (ref "U$1") (pin "38") (pinfunction "VSS_38") (pintype "bidirectional"))
      (node (ref "U$1") (pin "51") (pinfunction "VSS_51") (pintype "bidirectional"))
      (node (ref "U$1") (pin "61") (pinfunction "VSS_61") (pintype "bidirectional"))
      (node (ref "U$1") (pin "83") (pinfunction "VSS_83") (pintype "bidirectional"))
      (node (ref "U$1") (pin "94") (pinfunction "VSS_94") (pintype "bidirectional"))
      (node (ref "U$2") (pin "11") (pinfunction "GND_11_11") (pintype "bidirectional"))
      (node (ref "U$2") (pin "12") (pinfunction "REGN_12_12") (pintype "bidirectional"))
      (node (ref "U$2") (pin "13") (pinfunction "LODRV_13_13") (pintype "bidirectional"))
      (node (ref "U1") (pin "36") (pinfunction "AGND_36") (pintype "bidirectional"))
      (node (ref "U1") (pin "G1") (pinfunction "GND9_G1") (pintype "bidirectional"))
      (node (ref "U1") (pin "G2") (pinfunction "GND8_G2") (pintype "bidirectional"))
      (node (ref "U1") (pin "G3") (pinfunction "GND7_G3") (pintype "bidirectional"))
      (node (ref "U1") (pin "G4") (pinfunction "GND6_G4") (pintype "bidirectional"))
      (node (ref "U1") (pin "RFG1") (pinfunction "GND_RFG1") (pintype "bidirectional"))
      (node (ref "U1") (pin "RFG2") (pinfunction "GND1_RFG2") (pintype "bidirectional"))
      (node (ref "U1") (pin "RFG3") (pinfunction "GND2_RFG3") (pintype "bidirectional"))
      (node (ref "U1") (pin "RFG4") (pinfunction "GND3_RFG4") (pintype "bidirectional"))
      (node (ref "U1") (pin "RFG5") (pinfunction "GND4_RFG5") (pintype "bidirectional"))
      (node (ref "U1") (pin "RFG6") (pinfunction "GND5_RFG6") (pintype "bidirectional"))
      (node (ref "U3") (pin "1") (pinfunction "VSS_2_1") (pintype "power_in"))
      (node (ref "U3") (pin "12") (pinfunction "AVSS_12") (pintype "power_in"))
      (node (ref "U3") (pin "13") (pinfunction "VSS_13") (pintype "power_in"))
      (node (ref "U3") (pin "17") (pinfunction "EPAD_17") (pintype "power_in"))
      (node (ref "U4") (pin "27") (pinfunction "VSS_5_27") (pintype "input"))
      (node (ref "U4") (pin "29") (pinfunction "SCANEN_29") (pintype "output"))
      (node (ref "U4") (pin "33") (pinfunction "VSS_1_33") (pintype "passive"))
      (node (ref "U4") (pin "36") (pinfunction "VSS_4_36") (pintype "power_in"))
      (node (ref "U4") (pin "41") (pinfunction "VSS_3_41") (pintype "output"))
      (node (ref "U4") (pin "54") (pinfunction "VSS_2_54") (pintype "input"))
      (node (ref "USART3/FTDI") (pin "1") (pinfunction "1_1") (pintype "passive"))
      (node (ref "X4") (pin "2") (pinfunction "2_2") (pintype "passive"))
      (node (ref "XTAL3") (pin "GND") (pinfunction "GND_GND") (pintype "bidirectional"))
    )
    (net (code "126") (name "GPIO2") (class "Default")
      (node (ref "U1") (pin "2") (pinfunction "GPIO2_2") (pintype "bidirectional"))
    )
    (net (code "127") (name "GPIO3") (class "Default")
      (node (ref "U1") (pin "1") (pinfunction "GPIO3_1") (pintype "bidirectional"))
    )
    (net (code "128") (name "GPIO4") (class "Default")
      (node (ref "U1") (pin "4") (pinfunction "GPIO4_4") (pintype "bidirectional"))
    )
    (net (code "129") (name "GPIO5") (class "Default")
      (node (ref "U1") (pin "5") (pinfunction "GPIO5_5") (pintype "bidirectional"))
    )
    (net (code "130") (name "GPIO6") (class "Default")
      (node (ref "U1") (pin "18") (pinfunction "GPIO6_18") (pintype "bidirectional"))
    )
    (net (code "131") (name "GPIO7") (class "Default")
      (node (ref "U1") (pin "17") (pinfunction "GPIO7_17") (pintype "bidirectional"))
    )
    (net (code "132") (name "GPIO9") (class "Default")
      (node (ref "U1") (pin "10") (pinfunction "GPIO9_10") (pintype "bidirectional"))
    )
    (net (code "133") (name "GPIO10") (class "Default")
      (node (ref "U1") (pin "9") (pinfunction "GPIO10_9") (pintype "bidirectional"))
    )
    (net (code "134") (name "GPIO11") (class "Default")
      (node (ref "U1") (pin "8") (pinfunction "GPIO11_8") (pintype "bidirectional"))
    )
    (net (code "135") (name "GPIO12") (class "Default")
      (node (ref "U1") (pin "6") (pinfunction "GPIO12_6") (pintype "bidirectional"))
    )
    (net (code "136") (name "GPIO13") (class "Default")
      (node (ref "U1") (pin "7") (pinfunction "GPIO13_7") (pintype "bidirectional"))
    )
    (net (code "137") (name "LED0") (class "Default")
      (node (ref "D2") (pin "C") (pinfunction "C_C") (pintype "passive"))
      (node (ref "U1") (pin "30") (pinfunction "LED0_30") (pintype "bidirectional"))
    )
    (net (code "138") (name "LED1") (class "Default")
      (node (ref "D3") (pin "C") (pinfunction "C_C") (pintype "passive"))
      (node (ref "U1") (pin "29") (pinfunction "LED1_29") (pintype "bidirectional"))
    )
    (net (code "139") (name "MIC_BIAS") (class "Default")
      (node (ref "U1") (pin "31") (pinfunction "MIC_BIAS_31") (pintype "bidirectional"))
    )
    (net (code "140") (name "MIC_L+") (class "Default")
      (node (ref "U1") (pin "32") (pinfunction "MIC_L+_32") (pintype "bidirectional"))
    )
    (net (code "141") (name "MIC_L-") (class "Default")
      (node (ref "U1") (pin "34") (pinfunction "MIC_L-_34") (pintype "bidirectional"))
    )
    (net (code "142") (name "MIC_R+") (class "Default")
      (node (ref "U1") (pin "33") (pinfunction "MIC_R+_33") (pintype "bidirectional"))
    )
    (net (code "143") (name "MIC_R-") (class "Default")
      (node (ref "U1") (pin "35") (pinfunction "MIC_R-_35") (pintype "bidirectional"))
    )
    (net (code "144") (name "Net-(C25-Pad1)") (class "Default")
      (node (ref "C25") (pin "1") (pinfunction "1_1") (pintype "passive"))
      (node (ref "RI6") (pin "2") (pinfunction "2_2") (pintype "passive"))
    )
    (net (code "145") (name "Net-(C32-Pad1)") (class "Default")
      (node (ref "C32") (pin "1") (pinfunction "1_1") (pintype "passive"))
      (node (ref "C34") (pin "+") (pinfunction "+_+") (pintype "passive"))
      (node (ref "JP6") (pin "1") (pinfunction "1_1") (pintype "passive"))
      (node (ref "R18") (pin "2") (pinfunction "2_2") (pintype "passive"))
      (node (ref "TPS61028") (pin "2") (pinfunction "2_2") (pintype "passive"))
    )
    (net (code "146") (name "Net-(C33-Pad1)") (class "Default")
      (node (ref "C33") (pin "1") (pinfunction "1_1") (pintype "passive"))
      (node (ref "C35") (pin "+") (pinfunction "+_+") (pintype "passive"))
      (node (ref "C36") (pin "1") (pinfunction "1_1") (pintype "passive"))
      (node (ref "JP4") (pin "2") (pinfunction "2_2") (pintype "passive"))
      (node (ref "L4") (pin "1") (pinfunction "1_1") (pintype "passive"))
      (node (ref "R19") (pin "1") (pinfunction "1_1") (pintype "passive"))
      (node (ref "R20") (pin "2") (pinfunction "2_2") (pintype "passive"))
      (node (ref "TPS61028") (pin "7") (pinfunction "7_7") (pintype "passive"))
      (node (ref "TPS63031") (pin "5") (pinfunction "5_5") (pintype "passive"))
    )
    (net (code "147") (name "Net-(C37-Pad1)") (class "Default")
      (node (ref "C37") (pin "1") (pinfunction "1_1") (pintype "passive"))
      (node (ref "TPS63031") (pin "6") (pinfunction "6_6") (pintype "passive"))
      (node (ref "TPS63031") (pin "7") (pinfunction "7_7") (pintype "passive"))
      (node (ref "TPS63031") (pin "8") (pinfunction "8_8") (pintype "passive"))
    )
    (net (code "148") (name "Net-(C38-Pad1)") (class "Default")
      (node (ref "C38") (pin "1") (pinfunction "1_1") (pintype "passive"))
      (node (ref "C39") (pin "1") (pinfunction "1_1") (pintype "passive"))
      (node (ref "JP5") (pin "1") (pinfunction "1_1") (pintype "passive"))
      (node (ref "TPS63031") (pin "1") (pinfunction "1_1") (pintype "passive"))
      (node (ref "TPS63031") (pin "10") (pinfunction "10_10") (pintype "passive"))
    )
    (net (code "149") (name "Net-(D2-PadA)") (class "Default")
      (node (ref "D2") (pin "A") (pinfunction "A_A") (pintype "passive"))
      (node (ref "R5") (pin "1") (pinfunction "1_1") (pintype "passive"))
    )
    (net (code "150") (name "Net-(D3-PadA)") (class "Default")
      (node (ref "D3") (pin "A") (pinfunction "A_A") (pintype "passive"))
      (node (ref "R6") (pin "1") (pinfunction "1_1") (pintype "passive"))
    )
    (net (code "151") (name "Net-(D4-C)") (class "Default")
      (node (ref "D4") (pin "3") (pinfunction "C_3") (pintype "passive"))
      (node (ref "R8") (pin "2") (pinfunction "2_2") (pintype "passive"))
    )
    (net (code "152") (name "Net-(D6-PadC)") (class "Default")
      (node (ref "D6") (pin "C") (pinfunction "C_C") (pintype "passive"))
      (node (ref "IC8") (pin "1") (pinfunction "OUT_1") (pintype "output"))
      (node (ref "IC8") (pin "20") (pinfunction "OUT_20") (pintype "input"))
      (node (ref "L3") (pin "1") (pinfunction "1_1") (pintype "passive"))
    )
    (net (code "153") (name "Net-(IC8B-BAT)") (class "Default")
      (node (ref "IC8") (pin "14") (pinfunction "BAT_14") (pintype "input"))
      (node (ref "JP3") (pin "2") (pinfunction "2_2") (pintype "passive"))
      (node (ref "JP4") (pin "1") (pinfunction "1_1") (pintype "passive"))
      (node (ref "RSNS") (pin "2") (pinfunction "2_2") (pintype "passive"))
      (node (ref "X4") (pin "1") (pinfunction "1_1") (pintype "passive"))
    )
    (net (code "154") (name "Net-(IC8B-CELLS)") (class "Default")
      (node (ref "IC8") (pin "13") (pinfunction "CELLS_13") (pintype "input"))
      (node (ref "R10") (pin "1") (pinfunction "1_1") (pintype "passive"))
    )
    (net (code "155") (name "Net-(IC8B-IN1)") (class "Default")
      (node (ref "C26") (pin "1") (pinfunction "1_1") (pintype "passive"))
      (node (ref "CIN") (pin "1") (pinfunction "1_1") (pintype "passive"))
      (node (ref "IC8") (pin "3") (pinfunction "IN1_3") (pintype "input"))
      (node (ref "IC8") (pin "4") (pinfunction "IN2_4") (pintype "input"))
      (node (ref "IC8") (pin "6") (pinfunction "VCC_6") (pintype "input"))
      (node (ref "JP1") (pin "2") (pinfunction "2_2") (pintype "passive"))
      (node (ref "R10") (pin "2") (pinfunction "2_2") (pintype "passive"))
      (node (ref "R11") (pin "2") (pinfunction "2_2") (pintype "passive"))
      (node (ref "R12") (pin "2") (pinfunction "2_2") (pintype "passive"))
      (node (ref "R13") (pin "2") (pinfunction "2_2") (pintype "passive"))
    )
    (net (code "156") (name "Net-(IC8B-ISET1)") (class "Default")
      (node (ref "IC8") (pin "8") (pinfunction "ISET1_8") (pintype "bidirectional"))
      (node (ref "RI1") (pin "1") (pinfunction "1_1") (pintype "passive"))
    )
    (net (code "157") (name "Net-(IC8B-ISET2)") (class "Default")
      (node (ref "IC8") (pin "9") (pinfunction "ISET2_9") (pintype "bidirectional"))
      (node (ref "RI2") (pin "1") (pinfunction "1_1") (pintype "passive"))
    )
    (net (code "158") (name "Net-(IC8B-SNS)") (class "Default")
      (node (ref "CC") (pin "1") (pinfunction "1_1") (pintype "passive"))
      (node (ref "COUT") (pin "1") (pinfunction "1_1") (pintype "passive"))
      (node (ref "IC8") (pin "15") (pinfunction "SNS_15") (pintype "input"))
      (node (ref "L3") (pin "2") (pinfunction "2_2") (pintype "passive"))
      (node (ref "RSNS") (pin "1") (pinfunction "1_1") (pintype "passive"))
    )
    (net (code "159") (name "Net-(IC8B-STAT1)") (class "Default")
      (node (ref "IC8") (pin "2") (pinfunction "STAT1_2") (pintype "output"))
      (node (ref "LED1") (pin "K") (pinfunction "C_K") (pintype "passive"))
    )
    (net (code "160") (name "Net-(IC8B-STAT2)") (class "Default")
      (node (ref "IC8") (pin "19") (pinfunction "STAT2_19") (pintype "output"))
      (node (ref "LED2") (pin "K") (pinfunction "C_K") (pintype "passive"))
    )
    (net (code "161") (name "Net-(IC8B-TS)") (class "Default")
      (node (ref "IC8") (pin "12") (pinfunction "TS_12") (pintype "input"))
      (node (ref "RT1") (pin "1") (pinfunction "1_1") (pintype "passive"))
      (node (ref "RT2") (pin "2") (pinfunction "2_2") (pintype "passive"))
      (node (ref "RTHERMAL") (pin "1") (pinfunction "1_1") (pintype "passive"))
    )
    (net (code "162") (name "Net-(IC8B-TTC)") (class "Default")
      (node (ref "CTTC") (pin "1") (pinfunction "1_1") (pintype "passive"))
      (node (ref "IC8") (pin "7") (pinfunction "TTC_7") (pintype "passive"))
    )
    (net (code "163") (name "Net-(IC8B-VTSB)") (class "Default")
      (node (ref "CC1") (pin "1") (pinfunction "1_1") (pintype "passive"))
      (node (ref "IC8") (pin "11") (pinfunction "VTSB_11") (pintype "output"))
      (node (ref "RT1") (pin "2") (pinfunction "2_2") (pintype "passive"))
    )
    (net (code "164") (name "Net-(IC8B-~{PG})") (class "Default")
      (node (ref "IC8") (pin "5") (pinfunction "~{PG}_5") (pintype "output"))
      (node (ref "LED3") (pin "K") (pinfunction "C_K") (pintype "passive"))
    )
    (net (code "165") (name "Net-(J2-Pad2)") (class "Default")
      (node (ref "J2") (pin "2") (pinfunction "2_2") (pintype "passive"))
      (node (ref "JP1") (pin "1") (pinfunction "1_1") (pintype "passive"))
    )
    (net (code "166") (name "Net-(JP2-Pad7)") (class "Default")
      (node (ref "JP2") (pin "7") (pinfunction "7_7") (pintype "passive"))
      (node (ref "U5") (pin "CD2") (pinfunction "CD2_CD2") (pintype "bidirectional"))
    )
    (net (code "167") (name "Net-(L4-Pad2)") (class "Default")
      (node (ref "L4") (pin "2") (pinfunction "2_2") (pintype "passive"))
      (node (ref "TPS61028") (pin "9") (pinfunction "9_9") (pintype "passive"))
    )
    (net (code "168") (name "Net-(L7-Pad1)") (class "Default")
      (node (ref "L7") (pin "1") (pinfunction "1_1") (pintype "passive"))
      (node (ref "TPS63031") (pin "4") (pinfunction "4_4") (pintype "passive"))
    )
    (net (code "169") (name "Net-(L7-Pad2)") (class "Default")
      (node (ref "L7") (pin "2") (pinfunction "2_2") (pintype "passive"))
      (node (ref "TPS63031") (pin "2") (pinfunction "2_2") (pintype "passive"))
    )
    (net (code "170") (name "Net-(LED1-PadA)") (class "Default")
      (node (ref "LED1") (pin "A") (pinfunction "A_A") (pintype "passive"))
      (node (ref "R11") (pin "1") (pinfunction "1_1") (pintype "passive"))
    )
    (net (code "171") (name "Net-(LED2-PadA)") (class "Default")
      (node (ref "LED2") (pin "A") (pinfunction "A_A") (pintype "passive"))
      (node (ref "R12") (pin "1") (pinfunction "1_1") (pintype "passive"))
    )
    (net (code "172") (name "Net-(LED3-PadA)") (class "Default")
      (node (ref "LED3") (pin "A") (pinfunction "A_A") (pintype "passive"))
      (node (ref "R13") (pin "1") (pinfunction "1_1") (pintype "passive"))
    )
    (net (code "173") (name "Net-(LED7-PadC)") (class "Default")
      (node (ref "LED7") (pin "C") (pinfunction "C_C") (pintype "passive"))
      (node (ref "R4") (pin "2") (pinfunction "2_2") (pintype "passive"))
    )
    (net (code "174") (name "Net-(R15-Pad2)") (class "Default")
      (node (ref "R15") (pin "2") (pinfunction "2_2") (pintype "passive"))
      (node (ref "R16") (pin "2") (pinfunction "2_2") (pintype "passive"))
      (node (ref "R17") (pin "2") (pinfunction "2_2") (pintype "passive"))
    )
    (net (code "175") (name "Net-(R18-Pad1)") (class "Default")
      (node (ref "R18") (pin "1") (pinfunction "1_1") (pintype "passive"))
      (node (ref "TPS61028") (pin "4") (pinfunction "4_4") (pintype "passive"))
    )
    (net (code "176") (name "Net-(R19-Pad2)") (class "Default")
      (node (ref "R19") (pin "2") (pinfunction "2_2") (pintype "passive"))
      (node (ref "TPS61028") (pin "1") (pinfunction "1_1") (pintype "passive"))
      (node (ref "TPS61028") (pin "6") (pinfunction "6_6") (pintype "passive"))
    )
    (net (code "177") (name "Net-(R22-Pad1)") (class "Default")
      (node (ref "R22") (pin "1") (pinfunction "1_1") (pintype "passive"))
      (node (ref "R23") (pin "2") (pinfunction "2_2") (pintype "passive"))
      (node (ref "R24") (pin "2") (pinfunction "2_2") (pintype "passive"))
    )
    (net (code "178") (name "Net-(R26-Pad1)") (class "Default")
      (node (ref "R26") (pin "1") (pinfunction "1_1") (pintype "passive"))
      (node (ref "R27") (pin "2") (pinfunction "2_2") (pintype "passive"))
      (node (ref "R28") (pin "2") (pinfunction "2_2") (pintype "passive"))
    )
    (net (code "179") (name "Net-(R31-Pad2)") (class "Default")
      (node (ref "R31") (pin "2") (pinfunction "2_2") (pintype "passive"))
      (node (ref "R32") (pin "1") (pinfunction "1_1") (pintype "passive"))
    )
    (net (code "180") (name "Net-(U$1-PC14)") (class "Default")
      (node (ref "C3") (pin "1") (pinfunction "1_1") (pintype "passive"))
      (node (ref "U$1") (pin "8") (pinfunction "PC14_8") (pintype "bidirectional"))
      (node (ref "XTAL3") (pin "1") (pinfunction "1_1") (pintype "passive"))
    )
    (net (code "181") (name "Net-(U$1-PC15)") (class "Default")
      (node (ref "C2") (pin "1") (pinfunction "1_1") (pintype "passive"))
      (node (ref "U$1") (pin "9") (pinfunction "PC15_9") (pintype "bidirectional"))
      (node (ref "XTAL3") (pin "2") (pinfunction "2_2") (pintype "passive"))
    )
    (net (code "182") (name "Net-(U$2-VFB_8)") (class "Default")
      (node (ref "C31") (pin "1") (pinfunction "1_1") (pintype "passive"))
      (node (ref "U$2") (pin "8") (pinfunction "VFB_8_8") (pintype "bidirectional"))
    )
    (net (code "183") (name "Net-(U3-LBST)") (class "Default")
      (node (ref "L1") (pin "2") (pinfunction "2_2") (pintype "passive"))
      (node (ref "U3") (pin "16") (pinfunction "LBST_16") (pintype "input"))
    )
    (net (code "184") (name "Net-(U3-OK_HYST)") (class "Default")
      (node (ref "R14") (pin "1") (pinfunction "1_1") (pintype "passive"))
      (node (ref "R3") (pin "2") (pinfunction "2_2") (pintype "passive"))
      (node (ref "U3") (pin "9") (pinfunction "OK_HYST_9") (pintype "input"))
    )
    (net (code "185") (name "Net-(U3-OK_PROG)") (class "Default")
      (node (ref "R14") (pin "2") (pinfunction "2_2") (pintype "passive"))
      (node (ref "R15") (pin "1") (pinfunction "1_1") (pintype "passive"))
      (node (ref "U3") (pin "10") (pinfunction "OK_PROG_10") (pintype "input"))
    )
    (net (code "186") (name "Net-(U3-OT_PROG)") (class "Default")
      (node (ref "R29") (pin "2") (pinfunction "2_2") (pintype "passive"))
      (node (ref "R30") (pin "1") (pinfunction "1_1") (pintype "passive"))
      (node (ref "U3") (pin "5") (pinfunction "OT_PROG_5") (pintype "input"))
    )
    (net (code "187") (name "Net-(U3-VBAT)") (class "Default")
      (node (ref "C27_1812") (pin "1") (pinfunction "1_1") (pintype "passive"))
      (node (ref "JP3") (pin "1") (pinfunction "1_1") (pintype "passive"))
      (node (ref "U3") (pin "14") (pinfunction "VBAT_14") (pintype "bidirectional"))
    )
    (net (code "188") (name "Net-(U3-VBAT_OV)") (class "Default")
      (node (ref "R25") (pin "1") (pinfunction "1_1") (pintype "passive"))
      (node (ref "R26") (pin "2") (pinfunction "2_2") (pintype "passive"))
      (node (ref "U3") (pin "6") (pinfunction "VBAT_OV_6") (pintype "input"))
    )
    (net (code "189") (name "Net-(U3-VBAT_UV)") (class "Default")
      (node (ref "R21") (pin "1") (pinfunction "1_1") (pintype "passive"))
      (node (ref "R22") (pin "2") (pinfunction "2_2") (pintype "passive"))
      (node (ref "U3") (pin "8") (pinfunction "VBAT_UV_8") (pintype "input"))
    )
    (net (code "190") (name "Net-(U3-VIN_DC)") (class "Default")
      (node (ref "CTTC2") (pin "1") (pinfunction "1_1") (pintype "passive"))
      (node (ref "CTTC3") (pin "1") (pinfunction "1_1") (pintype "passive"))
      (node (ref "J1") (pin "2") (pinfunction "2_2") (pintype "passive"))
      (node (ref "L1") (pin "1") (pinfunction "1_1") (pintype "passive"))
      (node (ref "R33") (pin "2") (pinfunction "2_2") (pintype "passive"))
      (node (ref "U3") (pin "2") (pinfunction "VIN_DC_2") (pintype "input"))
    )
    (net (code "191") (name "Net-(U3-VOC_SAMP)") (class "Default")
      (node (ref "R32") (pin "2") (pinfunction "2_2") (pintype "passive"))
      (node (ref "R33") (pin "1") (pinfunction "1_1") (pintype "passive"))
      (node (ref "U3") (pin "3") (pinfunction "VOC_SAMP_3") (pintype "input"))
    )
    (net (code "192") (name "Net-(U3-VRDIV)") (class "Default")
      (node (ref "R21") (pin "2") (pinfunction "2_2") (pintype "passive"))
      (node (ref "R25") (pin "2") (pinfunction "2_2") (pintype "passive"))
      (node (ref "R3") (pin "1") (pinfunction "1_1") (pintype "passive"))
      (node (ref "U3") (pin "7") (pinfunction "VRDIV_7") (pintype "output"))
    )
    (net (code "193") (name "Net-(U3-VREF_SAMP)") (class "Default")
      (node (ref "CTTC1") (pin "1") (pinfunction "1_1") (pintype "passive"))
      (node (ref "U3") (pin "4") (pinfunction "VREF_SAMP_4") (pintype "input"))
    )
    (net (code "194") (name "Net-(U3-VSTOR)") (class "Default")
      (node (ref "CTTC4") (pin "1") (pinfunction "1_1") (pintype "passive"))
      (node (ref "CTTC5") (pin "1") (pinfunction "1_1") (pintype "passive"))
      (node (ref "R30") (pin "2") (pinfunction "2_2") (pintype "passive"))
      (node (ref "U3") (pin "15") (pinfunction "VSTOR_15") (pintype "output"))
    )
    (net (code "195") (name "Net-(U4-FILT)") (class "Default")
      (node (ref "C23") (pin "1") (pinfunction "1_1") (pintype "passive"))
      (node (ref "RI6") (pin "1") (pinfunction "1_1") (pintype "passive"))
      (node (ref "U4") (pin "37") (pinfunction "FILT_37") (pintype "passive"))
    )
    (net (code "196") (name "Net-(U4-PVDD)") (class "Default")
      (node (ref "C22") (pin "2") (pinfunction "2_2") (pintype "passive"))
      (node (ref "RI4") (pin "1") (pinfunction "1_1") (pintype "passive"))
      (node (ref "U4") (pin "39") (pinfunction "PVDD_39") (pintype "passive"))
    )
    (net (code "197") (name "Net-(U4-PVSS)") (class "Default")
      (node (ref "C22") (pin "1") (pinfunction "1_1") (pintype "passive"))
      (node (ref "RI5") (pin "2") (pinfunction "2_2") (pintype "passive"))
      (node (ref "U4") (pin "40") (pinfunction "PVSS_40") (pintype "passive"))
    )
    (net (code "198") (name "Net-(U4-XTI)") (class "Default")
      (node (ref "C18") (pin "1") (pinfunction "1_1") (pintype "passive"))
      (node (ref "Q1") (pin "1") (pinfunction "1_1") (pintype "passive"))
      (node (ref "RI3") (pin "1") (pinfunction "1_1") (pintype "passive"))
      (node (ref "U4") (pin "35") (pinfunction "XTI_35") (pintype "power_in"))
    )
    (net (code "199") (name "Net-(U4-XTO)") (class "Default")
      (node (ref "C19") (pin "1") (pinfunction "1_1") (pintype "passive"))
      (node (ref "Q1") (pin "2") (pinfunction "2_2") (pintype "passive"))
      (node (ref "RI3") (pin "2") (pinfunction "2_2") (pintype "passive"))
      (node (ref "U4") (pin "38") (pinfunction "XTO_38") (pintype "input"))
    )
    (net (code "200") (name "Net-(U5-CS)") (class "Default")
      (node (ref "JP2") (pin "1") (pinfunction "1_1") (pintype "passive"))
      (node (ref "U5") (pin "2") (pinfunction "CS_2") (pintype "bidirectional"))
    )
    (net (code "201") (name "Net-(U5-GND)") (class "Default")
      (node (ref "JP2") (pin "5") (pinfunction "5_5") (pintype "passive"))
      (node (ref "U5") (pin "6") (pinfunction "GND_6") (pintype "bidirectional"))
      (node (ref "U5") (pin "GND1") (pinfunction "SHIELD1_GND1") (pintype "bidirectional"))
      (node (ref "U5") (pin "GND2") (pinfunction "SHIELD2_GND2") (pintype "bidirectional"))
    )
    (net (code "202") (name "Net-(U5-SCK)") (class "Default")
      (node (ref "JP2") (pin "4") (pinfunction "4_4") (pintype "passive"))
      (node (ref "U5") (pin "5") (pinfunction "SCK_5") (pintype "bidirectional"))
    )
    (net (code "203") (name "PCM_CLK") (class "Default")
      (node (ref "U1") (pin "24") (pinfunction "PCM_CLK_24") (pintype "bidirectional"))
      (node (ref "U4") (pin "49") (pinfunction "SCKT_49") (pintype "passive"))
    )
    (net (code "204") (name "PCM_IN") (class "Default")
      (node (ref "U1") (pin "21") (pinfunction "PCM_IN_21") (pintype "bidirectional"))
      (node (ref "U4") (pin "50") (pinfunction "SDO_50") (pintype "input"))
    )
    (net (code "205") (name "PCM_SYNC") (class "Default")
      (node (ref "U1") (pin "23") (pinfunction "PCM_SYNC_23") (pintype "bidirectional"))
      (node (ref "U4") (pin "52") (pinfunction "LRCKT_52") (pintype "passive"))
    )
    (net (code "206") (name "PWREN") (class "Default")
      (node (ref "U1") (pin "19") (pinfunction "PWREN_19") (pintype "bidirectional"))
    )
    (net (code "207") (name "SPI_CLK") (class "Default")
      (node (ref "U1") (pin "27") (pinfunction "SPI_CLK_27") (pintype "bidirectional"))
    )
    (net (code "208") (name "SPI_MISO") (class "Default")
      (node (ref "U1") (pin "26") (pinfunction "SPI_MISO_26") (pintype "bidirectional"))
    )
    (net (code "209") (name "SPI_MOSI") (class "Default")
      (node (ref "U1") (pin "28") (pinfunction "SPI_MOSI_28") (pintype "bidirectional"))
    )
    (net (code "210") (name "SPI_SS") (class "Default")
      (node (ref "U1") (pin "25") (pinfunction "SPI_SS_25") (pintype "bidirectional"))
    )
    (net (code "211") (name "SPKR_L+") (class "Default")
      (node (ref "U1") (pin "40") (pinfunction "SPKR_L+_40") (pintype "bidirectional"))
    )
    (net (code "212") (name "SPKR_L-") (class "Default")
      (node (ref "U1") (pin "38") (pinfunction "SPKR_L-_38") (pintype "bidirectional"))
    )
    (net (code "213") (name "SPKR_R+") (class "Default")
      (node (ref "U1") (pin "39") (pinfunction "SPKR_R+_39") (pintype "bidirectional"))
    )
    (net (code "214") (name "SPKR_R-") (class "Default")
      (node (ref "U1") (pin "37") (pinfunction "SPKR_R-_37") (pintype "bidirectional"))
    )
    (net (code "215") (name "UART_CTS") (class "Default")
      (node (ref "U1") (pin "14") (pinfunction "UART_CTS_14") (pintype "bidirectional"))
    )
    (net (code "216") (name "UART_RTS") (class "Default")
      (node (ref "U1") (pin "13") (pinfunction "UART_RTS_13") (pintype "bidirectional"))
    )
    (net (code "217") (name "UART_RX") (class "Default")
      (node (ref "U1") (pin "16") (pinfunction "UART_RX_16") (pintype "bidirectional"))
    )
    (net (code "218") (name "UART_TX") (class "Default")
      (node (ref "U1") (pin "15") (pinfunction "UART_TX_15") (pintype "bidirectional"))
    )
    (net (code "219") (name "USBD+") (class "Default")
      (node (ref "U1") (pin "12") (pinfunction "USBD+_12") (pintype "bidirectional"))
    )
    (net (code "220") (name "USBD-") (class "Default")
      (node (ref "U1") (pin "11") (pinfunction "USBD-_11") (pintype "bidirectional"))
    )
    (net (code "221") (name "unconnected-(BOOTLOAD-Pad2)") (class "Default")
      (node (ref "BOOTLOAD") (pin "2") (pinfunction "2_2") (pintype "passive"))
    )
    (net (code "222") (name "unconnected-(BOOTLOAD-Pad6)") (class "Default")
      (node (ref "BOOTLOAD") (pin "6") (pinfunction "6_6") (pintype "passive"))
    )
    (net (code "223") (name "unconnected-(S1-Pad1)") (class "Default")
      (node (ref "S1") (pin "1") (pinfunction "1_1") (pintype "passive"))
    )
    (net (code "224") (name "unconnected-(S1-Pad3)") (class "Default")
      (node (ref "S1") (pin "3") (pinfunction "3_3") (pintype "passive"))
    )
    (net (code "225") (name "unconnected-(S2-Pad1)") (class "Default")
      (node (ref "S2") (pin "1") (pinfunction "1_1") (pintype "passive"))
    )
    (net (code "226") (name "unconnected-(S2-Pad3)") (class "Default")
      (node (ref "S2") (pin "3") (pinfunction "3_3") (pintype "passive"))
    )
    (net (code "227") (name "unconnected-(S3-Pad1)") (class "Default")
      (node (ref "S3") (pin "1") (pinfunction "1_1") (pintype "passive"))
    )
    (net (code "228") (name "unconnected-(S3-Pad3)") (class "Default")
      (node (ref "S3") (pin "3") (pinfunction "3_3") (pintype "passive"))
    )
    (net (code "229") (name "unconnected-(S4-Pad1)") (class "Default")
      (node (ref "S4") (pin "1") (pinfunction "1_1") (pintype "passive"))
    )
    (net (code "230") (name "unconnected-(S4-Pad3)") (class "Default")
      (node (ref "S4") (pin "3") (pinfunction "3_3") (pintype "passive"))
    )
    (net (code "231") (name "unconnected-(S5-Pad1)") (class "Default")
      (node (ref "S5") (pin "1") (pinfunction "1_1") (pintype "passive"))
    )
    (net (code "232") (name "unconnected-(S5-Pad3)") (class "Default")
      (node (ref "S5") (pin "3") (pinfunction "3_3") (pintype "passive"))
    )
    (net (code "233") (name "unconnected-(S6-Pad1)") (class "Default")
      (node (ref "S6") (pin "1") (pinfunction "1_1") (pintype "passive"))
    )
    (net (code "234") (name "unconnected-(S6-Pad3)") (class "Default")
      (node (ref "S6") (pin "3") (pinfunction "3_3") (pintype "passive"))
    )
    (net (code "235") (name "unconnected-(S7-Pad1)") (class "Default")
      (node (ref "S7") (pin "1") (pinfunction "1_1") (pintype "passive"))
    )
    (net (code "236") (name "unconnected-(S7-Pad3)") (class "Default")
      (node (ref "S7") (pin "3") (pinfunction "3_3") (pintype "passive"))
    )
    (net (code "237") (name "unconnected-(S8-Pad1)") (class "Default")
      (node (ref "S8") (pin "1") (pinfunction "1_1") (pintype "passive"))
    )
    (net (code "238") (name "unconnected-(S8-Pad3)") (class "Default")
      (node (ref "S8") (pin "3") (pinfunction "3_3") (pintype "passive"))
    )
    (net (code "239") (name "unconnected-(SV2-Pad5)") (class "Default")
      (node (ref "SV2") (pin "5") (pinfunction "5_5") (pintype "passive"))
    )
    (net (code "240") (name "unconnected-(TPS61028-Pad3)") (class "Default")
      (node (ref "TPS61028") (pin "3") (pinfunction "3_3") (pintype "passive"))
    )
    (net (code "241") (name "unconnected-(U$2-BTST_16-Pad16)") (class "Default")
      (node (ref "U$2") (pin "16") (pinfunction "BTST_16_16") (pintype "bidirectional"))
    )
    (net (code "242") (name "unconnected-(U$2-PH_14-Pad14)") (class "Default")
      (node (ref "U$2") (pin "14") (pinfunction "PH_14_14") (pintype "bidirectional"))
    )
    (net (code "243") (name "unconnected-(U$2-SRN_9-Pad9)") (class "Default")
      (node (ref "U$2") (pin "9") (pinfunction "SRN_9_9") (pintype "bidirectional"))
    )
    (net (code "244") (name "unconnected-(U$2-SRP_10-Pad10)") (class "Default")
      (node (ref "U$2") (pin "10") (pinfunction "SRP_10_10") (pintype "bidirectional"))
    )
    (net (code "245") (name "unconnected-(U$2-TS_4-Pad4)") (class "Default")
      (node (ref "U$2") (pin "4") (pinfunction "TS_4_4") (pintype "bidirectional"))
    )
    (net (code "246") (name "unconnected-(U1-PCM_OUT-Pad22)") (class "Default")
      (node (ref "U1") (pin "22") (pinfunction "PCM_OUT_22") (pintype "bidirectional"))
    )
    (net (code "247") (name "unconnected-(U3-VBAT_OK-Pad11)") (class "Default")
      (node (ref "U3") (pin "11") (pinfunction "VBAT_OK_11") (pintype "output"))
    )
    (net (code "248") (name "unconnected-(U4-OCLK-Pad51)") (class "Default")
      (node (ref "U4") (pin "51") (pinfunction "OCLK_51") (pintype "passive"))
    )
    (net (code "249") (name "unconnected-(U5-NC-Pad1)") (class "Default")
      (node (ref "U5") (pin "1") (pinfunction "NC_1") (pintype "bidirectional"))
    )
    (net (code "250") (name "unconnected-(U5-PadCD1)") (class "Default")
      (node (ref "U5") (pin "CD1") (pinfunction "CD1_CD1") (pintype "bidirectional"))
    )
    (net (code "251") (name "unconnected-(U5-RSV-Pad8)") (class "Default")
      (node (ref "U5") (pin "8") (pinfunction "RSV_8") (pintype "bidirectional"))
    )
    (net (code "252") (name "unconnected-(USART3/FTDI-Pad2)") (class "Default")
      (node (ref "USART3/FTDI") (pin "2") (pinfunction "2_2") (pintype "passive"))
    )
    (net (code "253") (name "unconnected-(USART3/FTDI-Pad6)") (class "Default")
      (node (ref "USART3/FTDI") (pin "6") (pinfunction "6_6") (pintype "passive"))
    )
  )
)
